# BatteryBoardV2.net
KiCad netlist of a schematic drawn in EAGLE
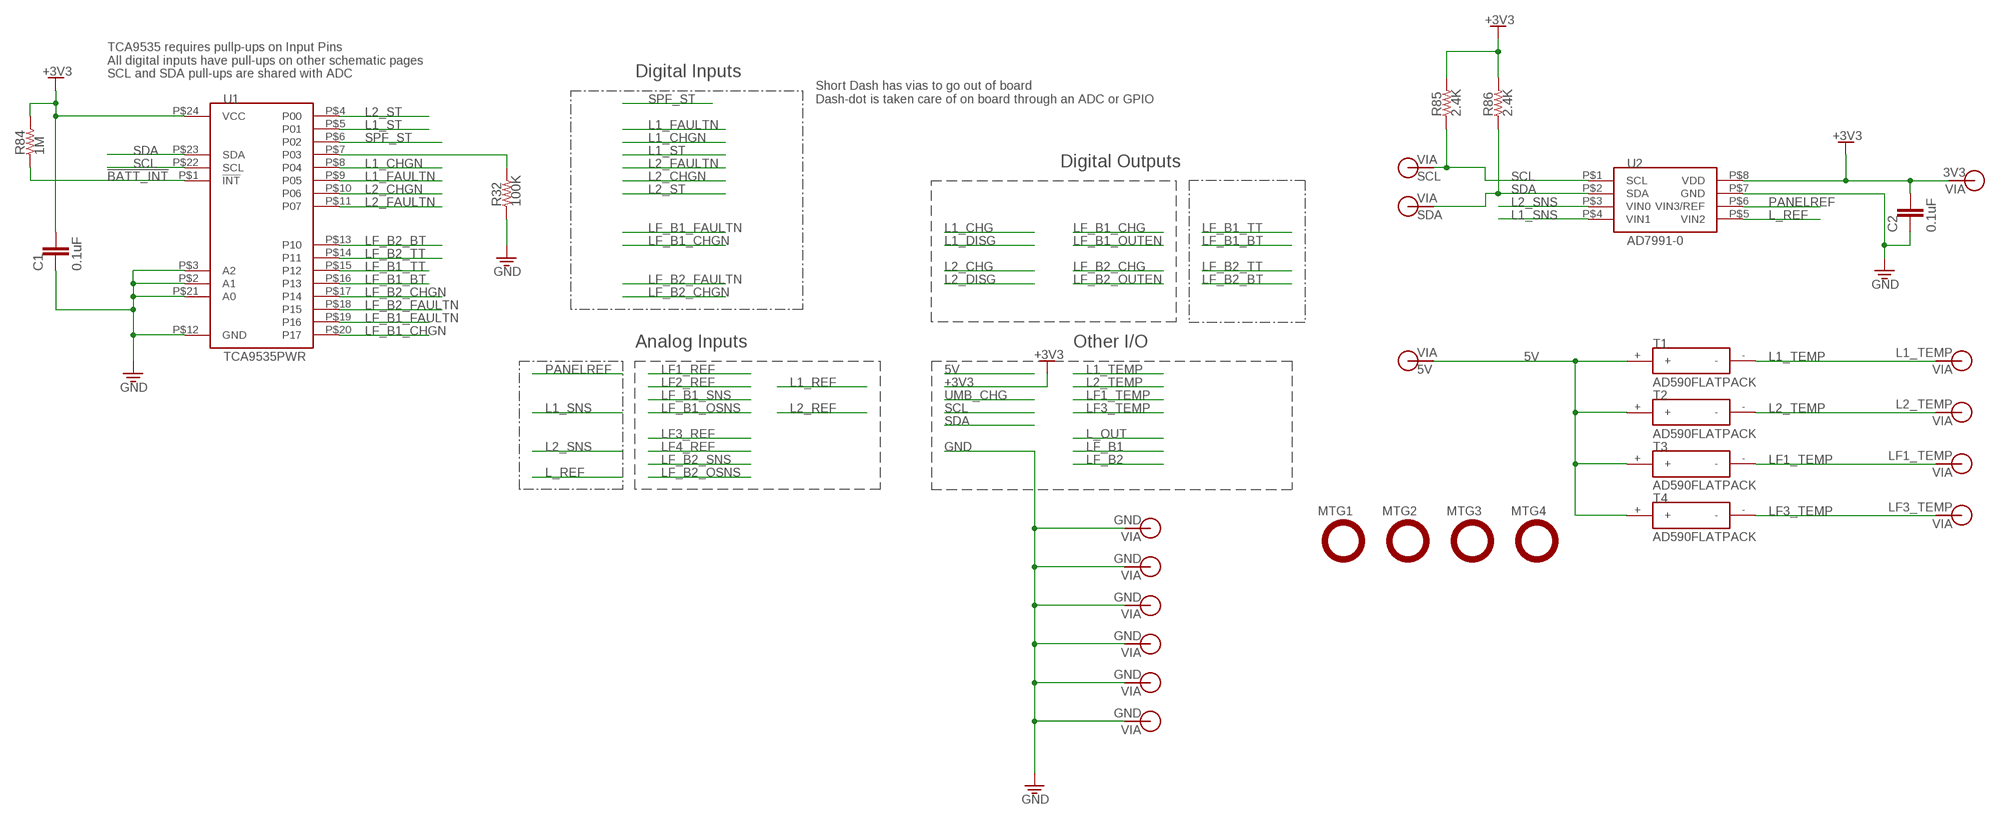
[diagram p0: schematic, sheet 1]
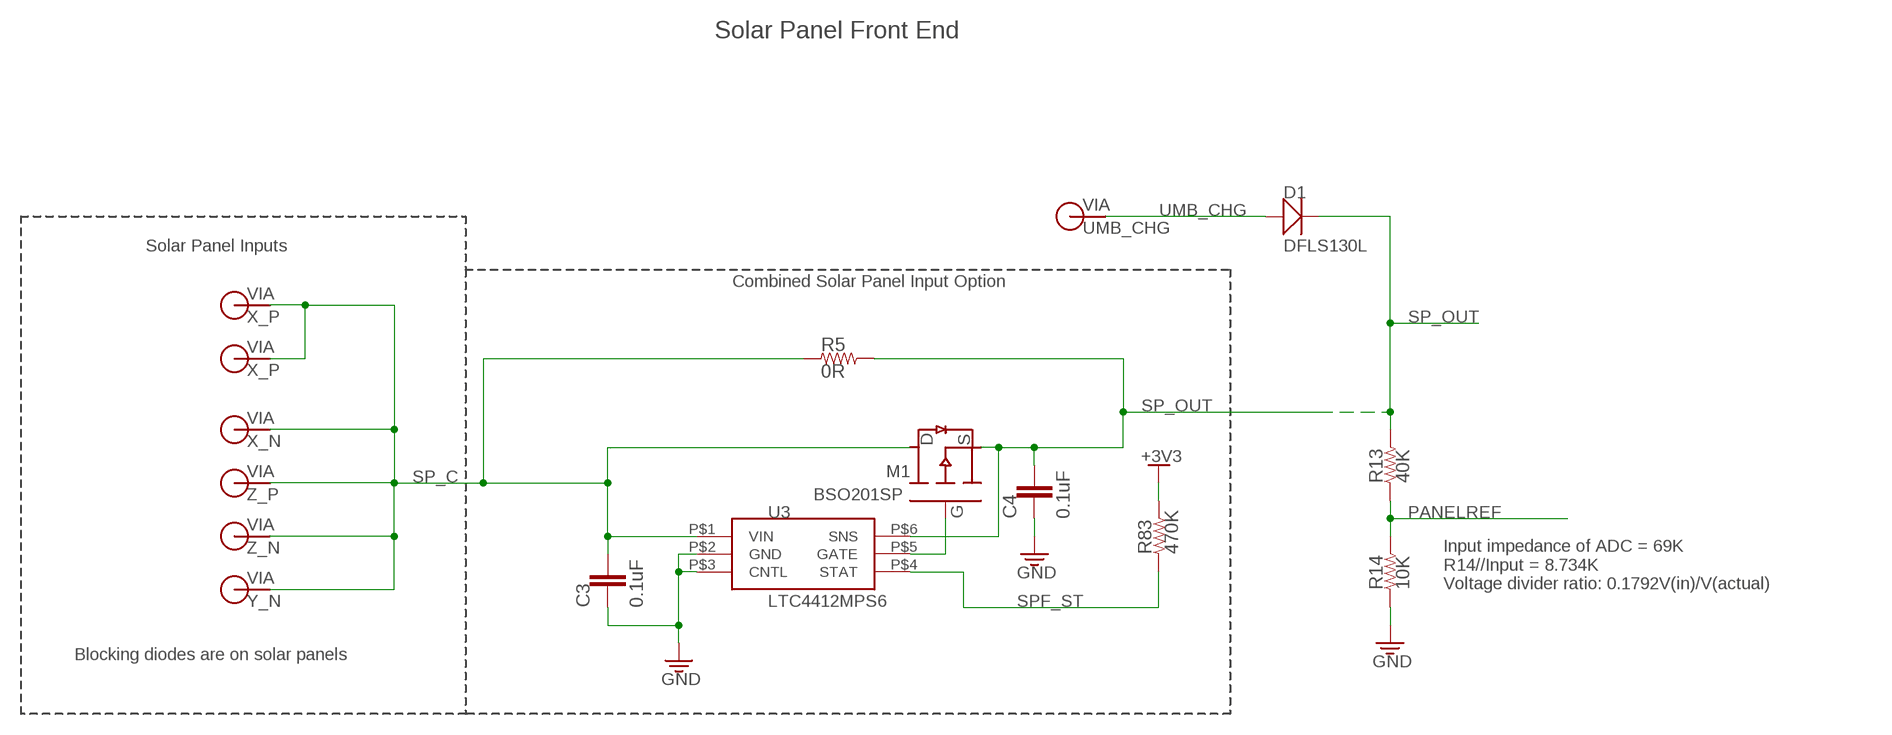
[diagram p1: schematic, sheet 2]
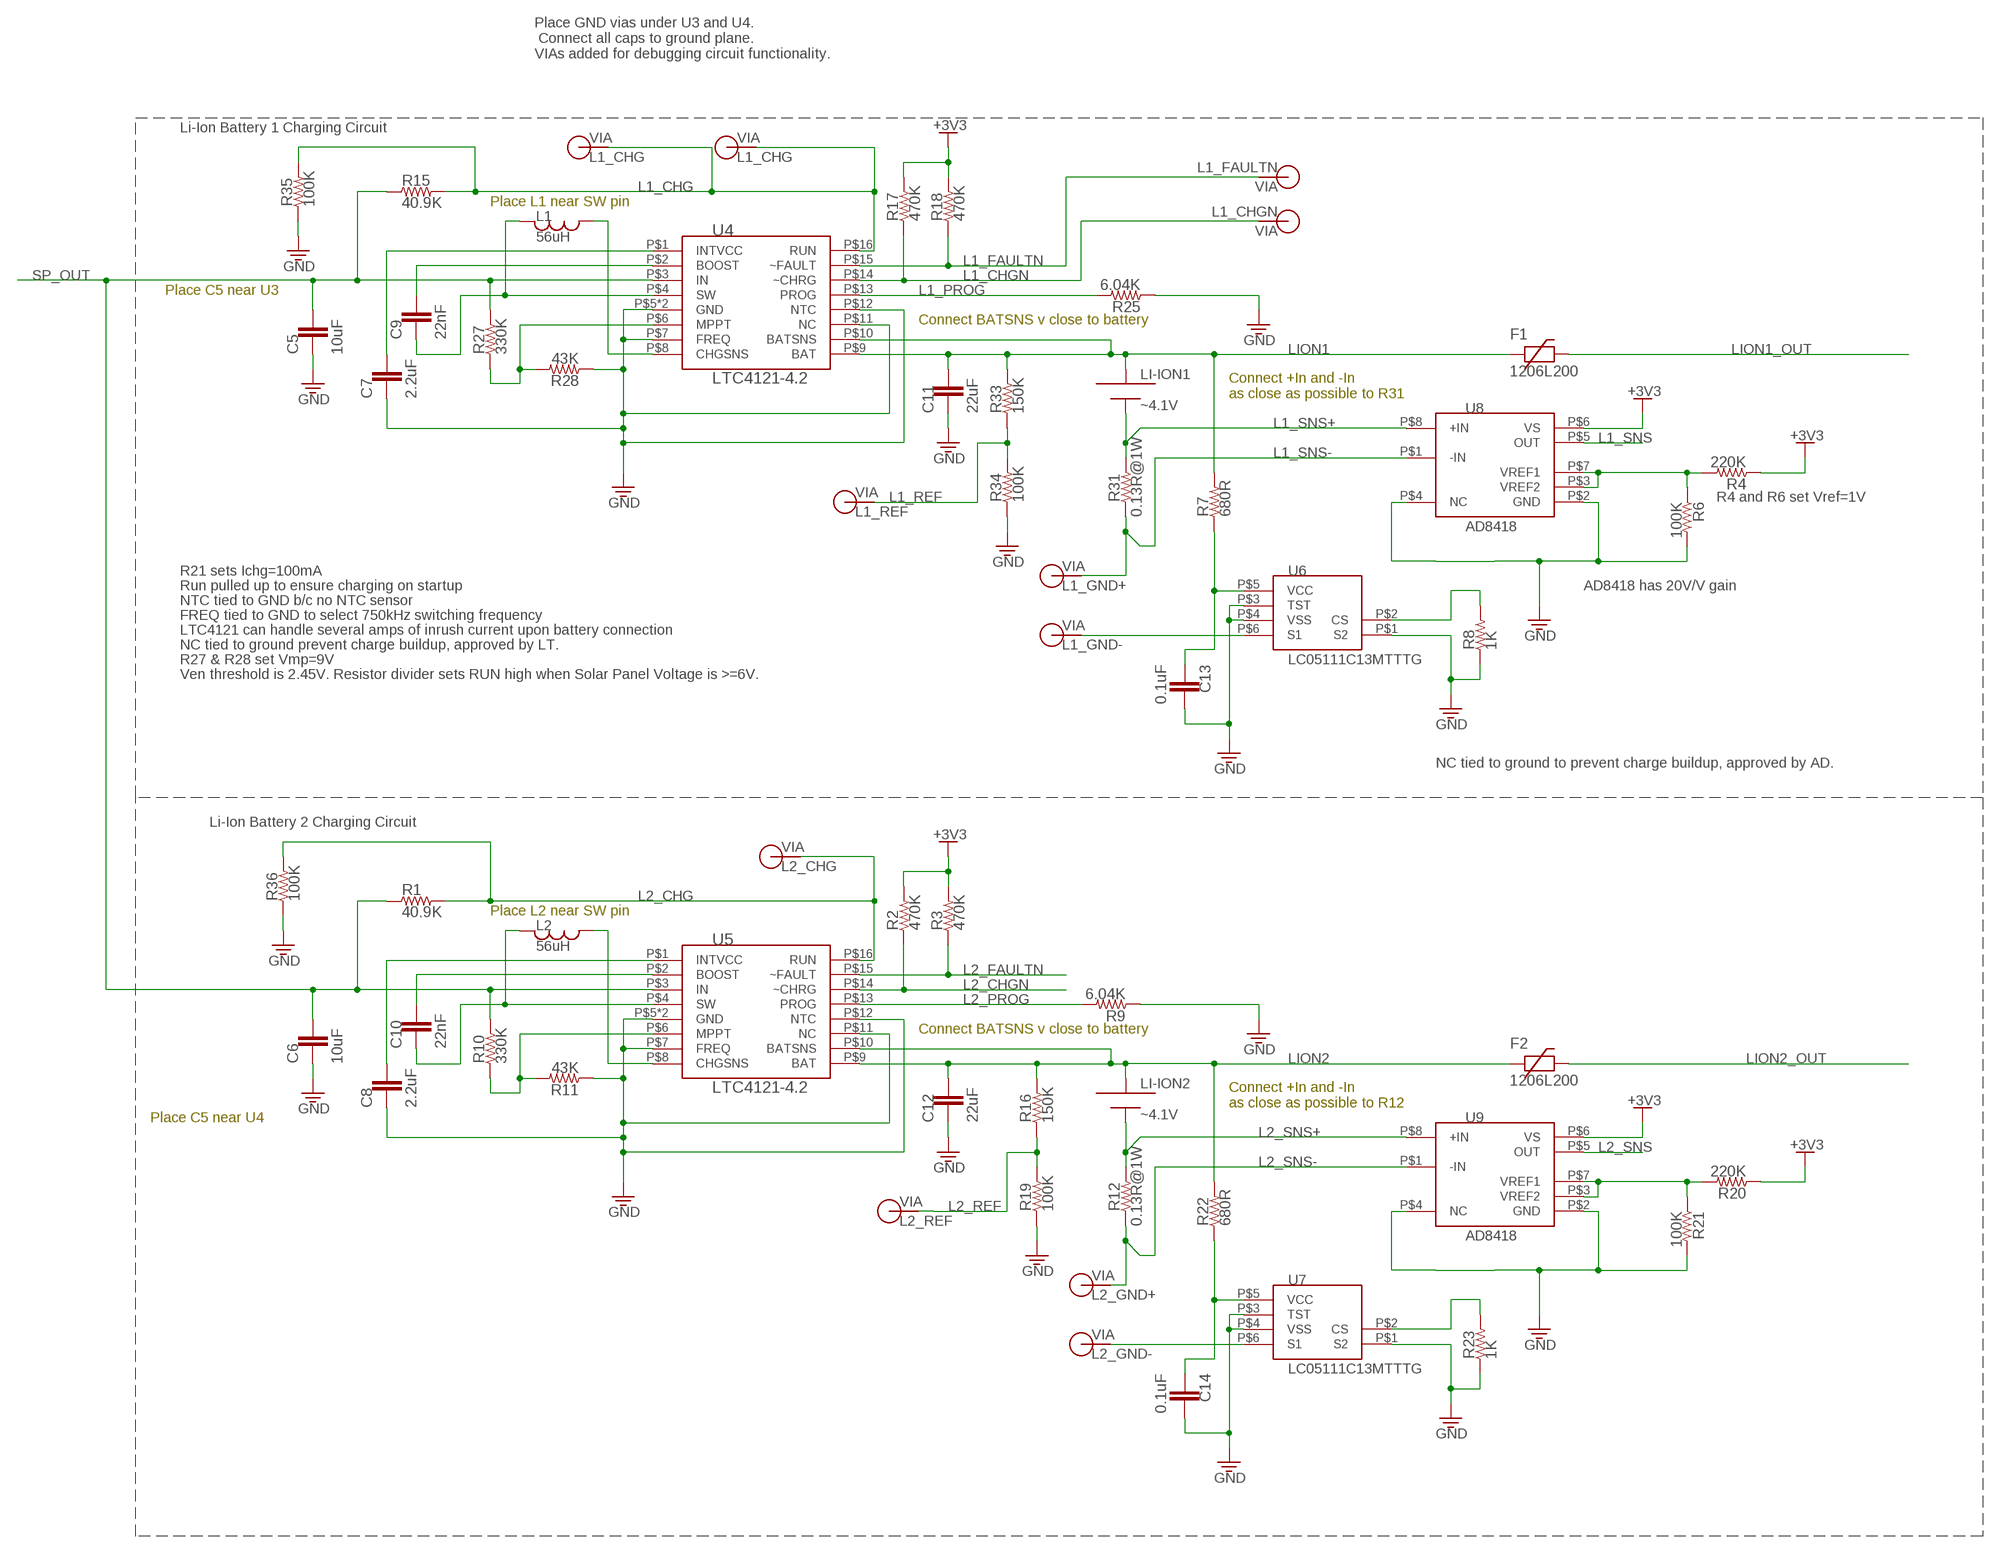
[diagram p2: schematic, sheet 3]
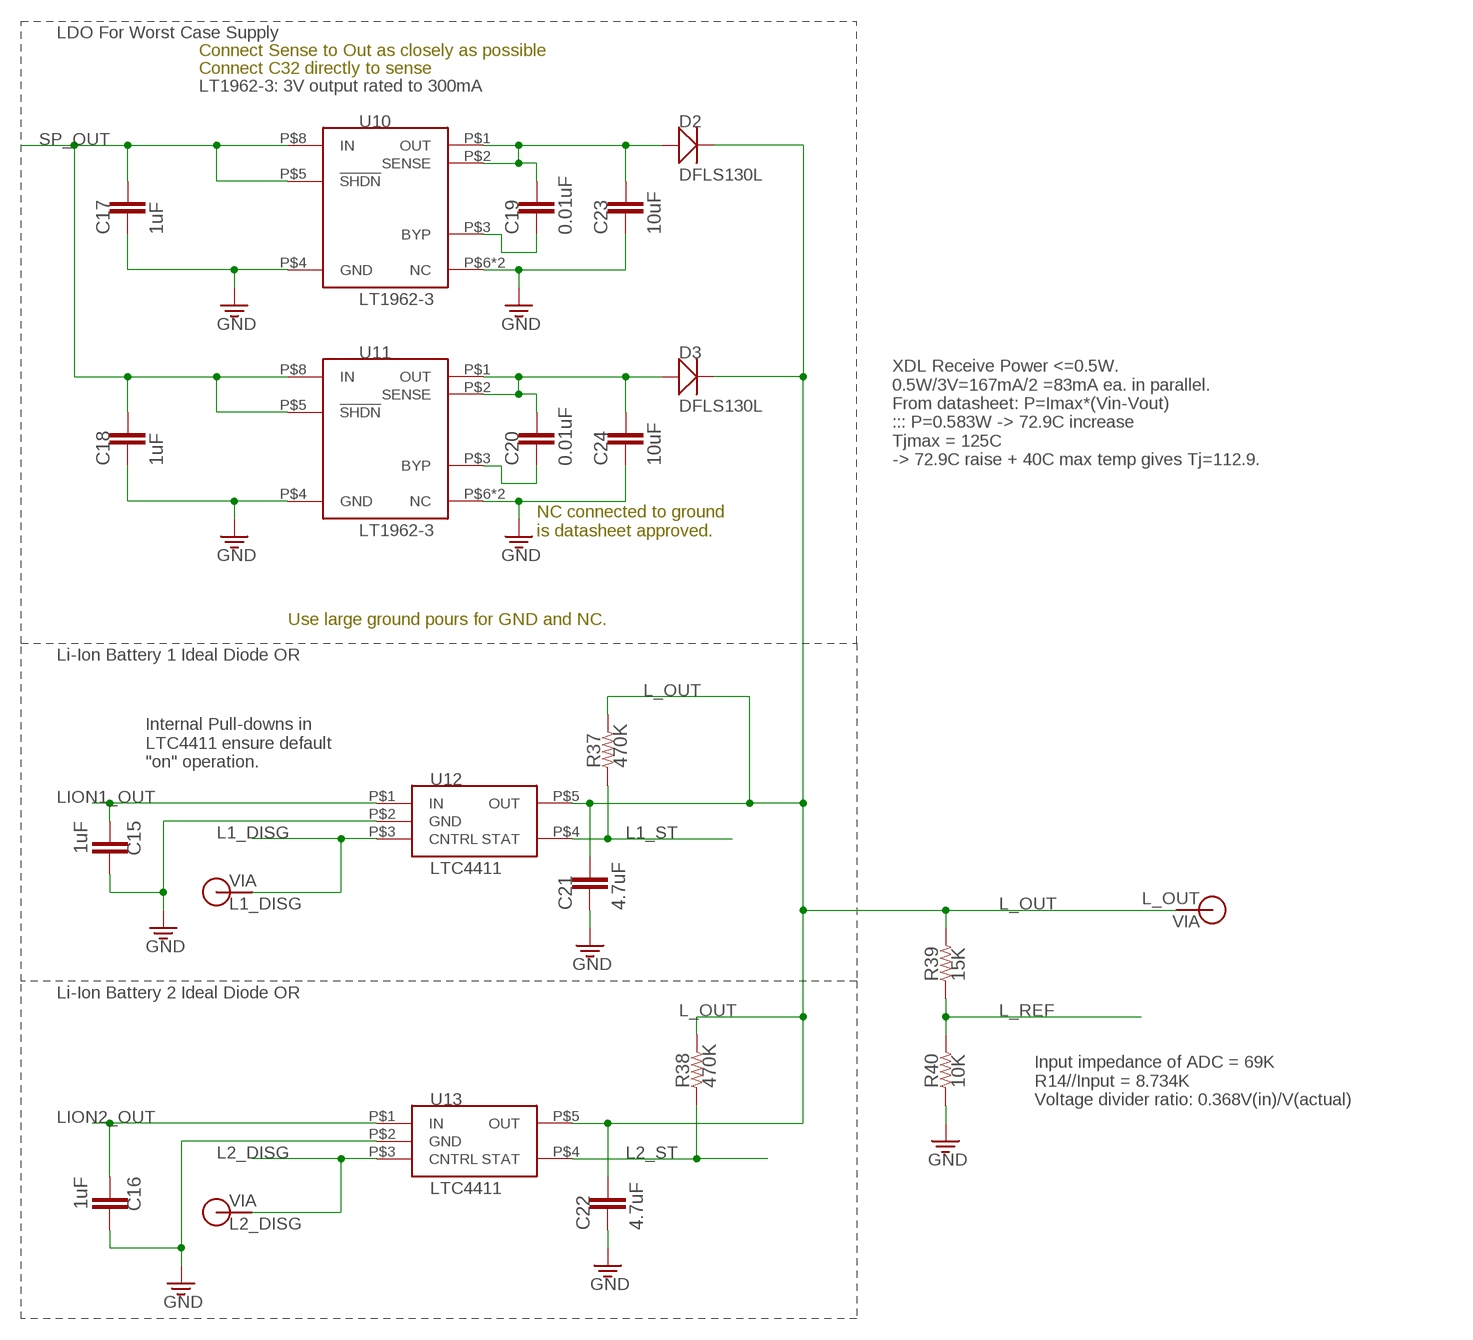
[diagram p3: schematic, sheet 4]
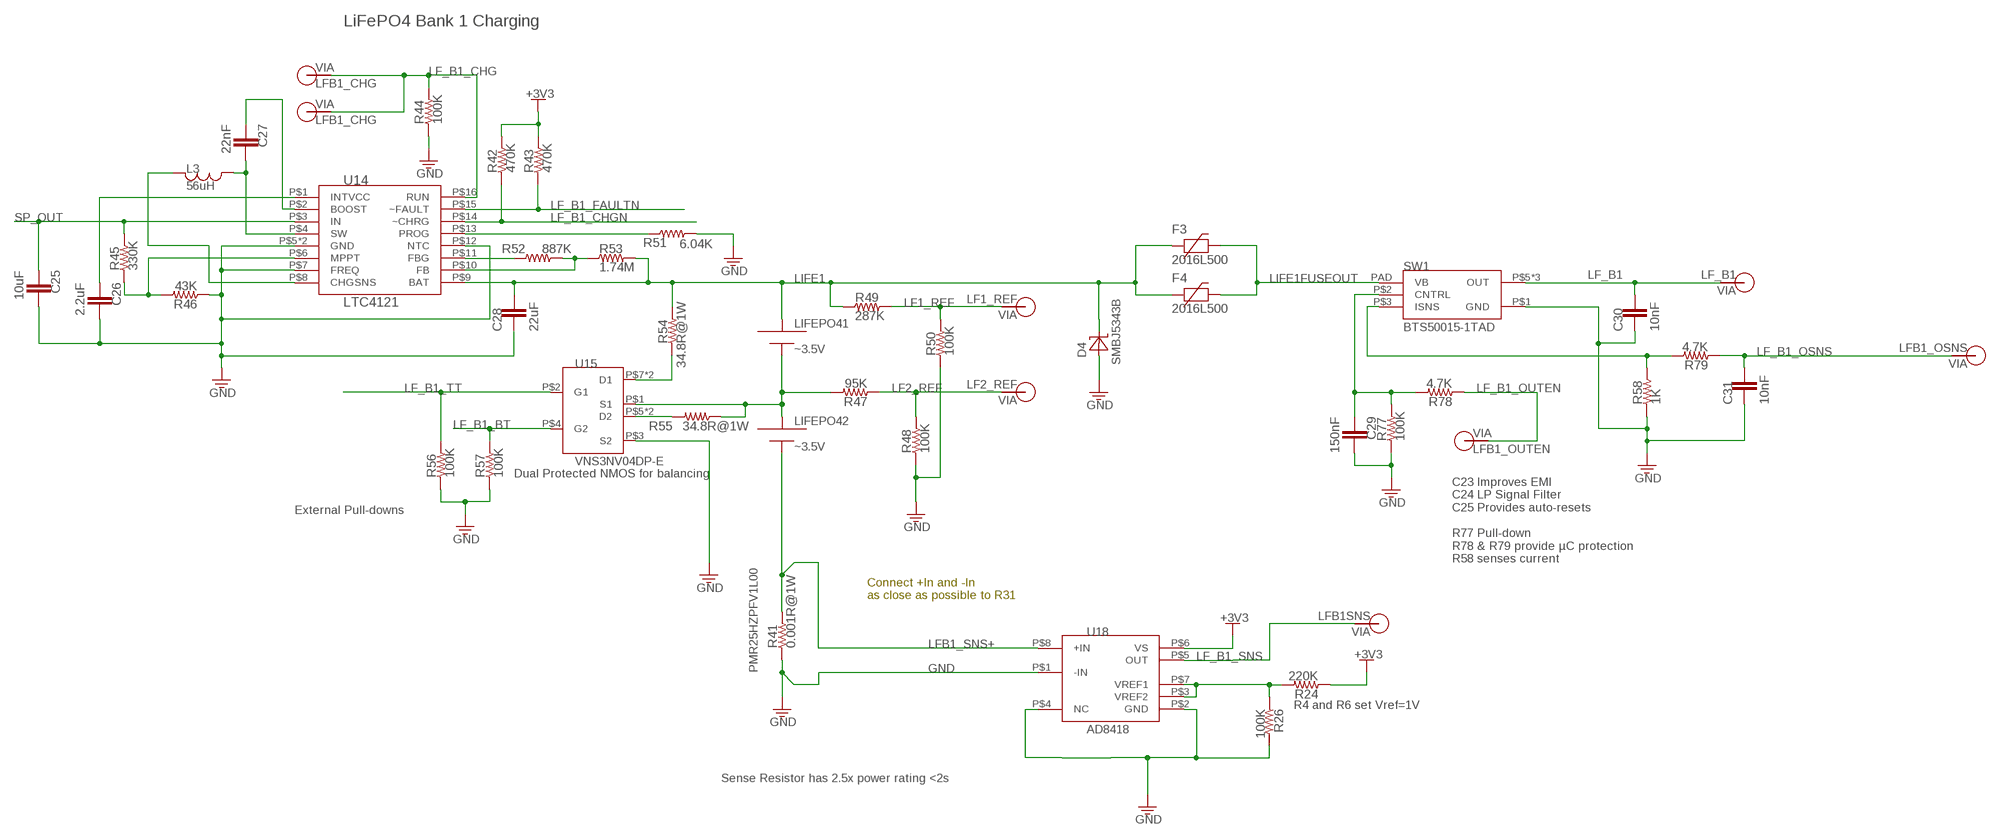
[diagram p4: schematic, sheet 5]
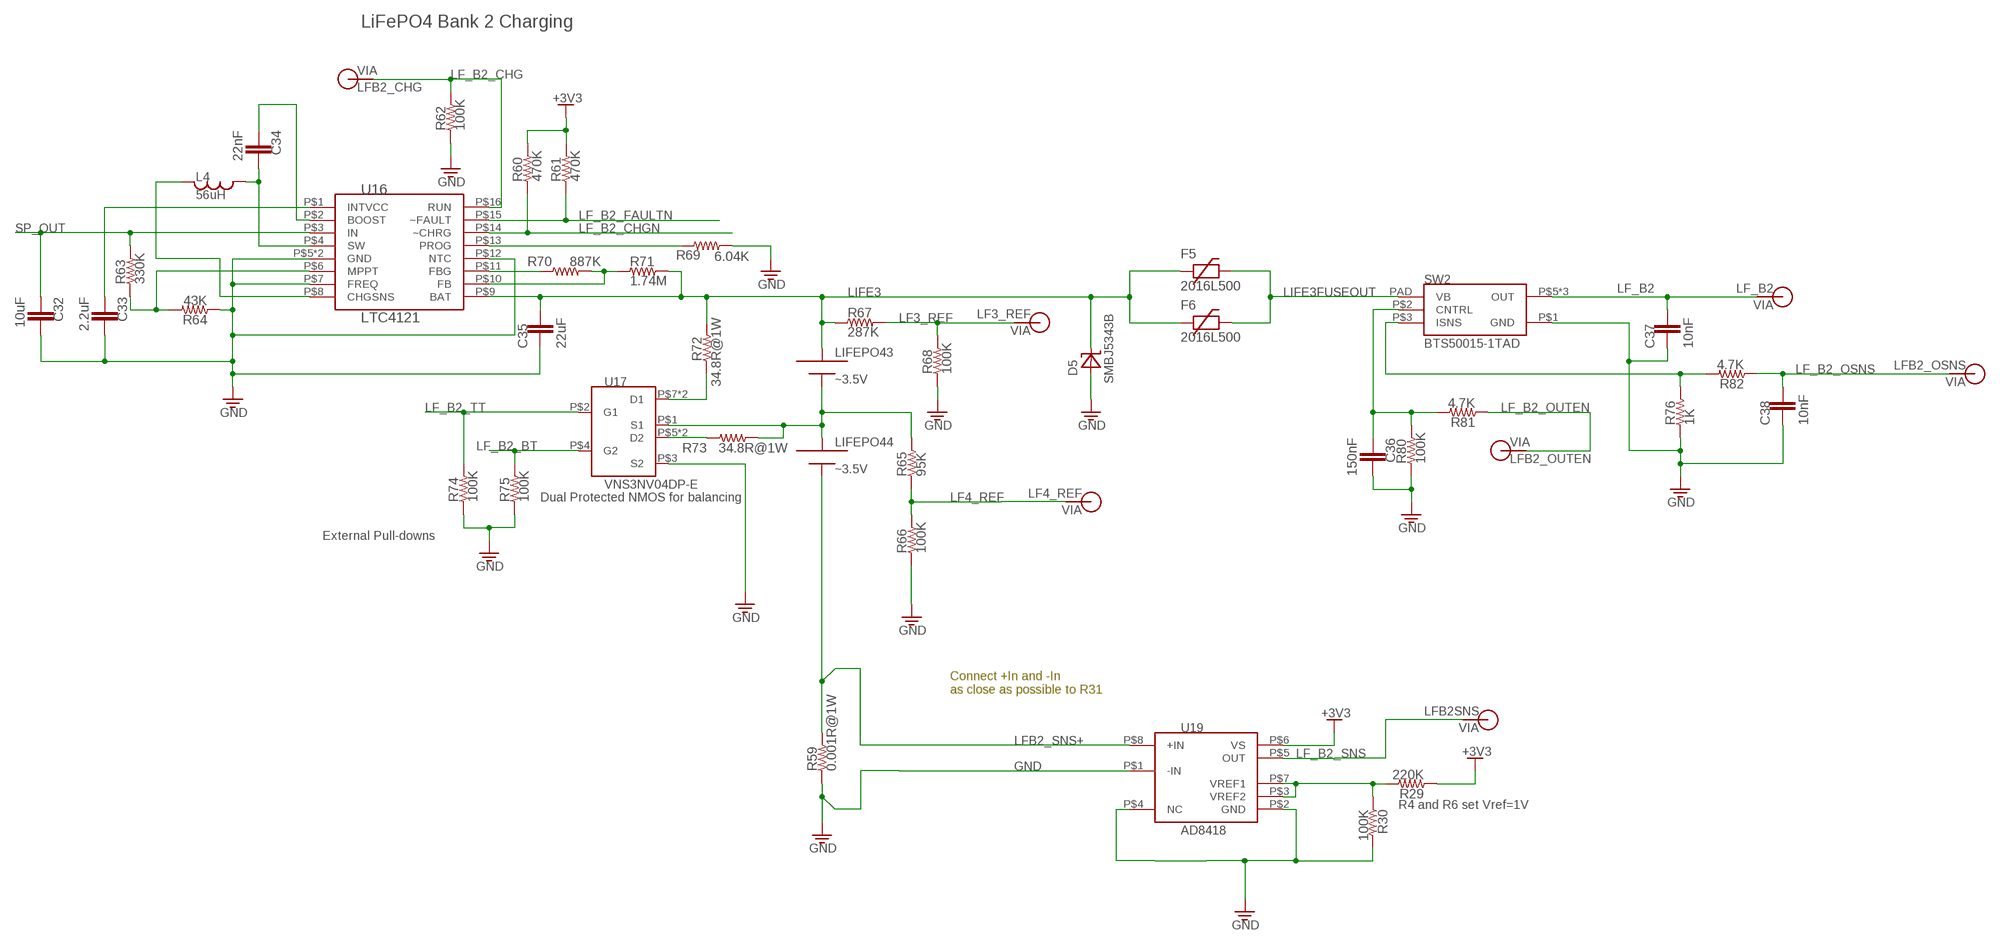
[diagram p5: schematic, sheet 6]

(export (version "E")
  (design (tool "Eeschema 10.0.6"))
  (components
    (comp (ref "C1")
      (value "0.1uF")
      (footprint "eagle-import:0805")
      (libsource (lib "eagle-import") (part "CAP0805"))
    )
    (comp (ref "C2")
      (value "0.1uF")
      (footprint "eagle-import:0805")
      (libsource (lib "eagle-import") (part "CAP0805"))
    )
    (comp (ref "MTG1")
      (value "MTG-NPTH-#2-CLOSE")
      (footprint "eagle-import:#2-CLOSE-NPTH")
      (libsource (lib "eagle-import") (part "MTG-NPTH-#2-CLOSE"))
    )
    (comp (ref "MTG2")
      (value "MTG-NPTH-#2-CLOSE")
      (footprint "eagle-import:#2-CLOSE-NPTH")
      (libsource (lib "eagle-import") (part "MTG-NPTH-#2-CLOSE"))
    )
    (comp (ref "MTG3")
      (value "MTG-NPTH-#2-CLOSE")
      (footprint "eagle-import:#2-CLOSE-NPTH")
      (libsource (lib "eagle-import") (part "MTG-NPTH-#2-CLOSE"))
    )
    (comp (ref "MTG4")
      (value "MTG-NPTH-#2-CLOSE")
      (footprint "eagle-import:#2-CLOSE-NPTH")
      (libsource (lib "eagle-import") (part "MTG-NPTH-#2-CLOSE"))
    )
    (comp (ref "R32")
      (value "100K")
      (footprint "eagle-import:0805")
      (libsource (lib "eagle-import") (part "RES0805"))
    )
    (comp (ref "R84")
      (value "1M")
      (footprint "eagle-import:0805")
      (libsource (lib "eagle-import") (part "RES0805"))
    )
    (comp (ref "R85")
      (value "2.4K")
      (footprint "eagle-import:0805")
      (libsource (lib "eagle-import") (part "RES0805"))
    )
    (comp (ref "R86")
      (value "2.4K")
      (footprint "eagle-import:0805")
      (libsource (lib "eagle-import") (part "RES0805"))
    )
    (comp (ref "T1")
      (value "AD590FLATPACK")
      (footprint "eagle-import:FLATPACK")
      (libsource (lib "eagle-import") (part "AD590FLATPACK"))
    )
    (comp (ref "T2")
      (value "AD590FLATPACK")
      (footprint "eagle-import:FLATPACK")
      (libsource (lib "eagle-import") (part "AD590FLATPACK"))
    )
    (comp (ref "T3")
      (value "AD590FLATPACK")
      (footprint "eagle-import:FLATPACK")
      (libsource (lib "eagle-import") (part "AD590FLATPACK"))
    )
    (comp (ref "T4")
      (value "AD590FLATPACK")
      (footprint "eagle-import:FLATPACK")
      (libsource (lib "eagle-import") (part "AD590FLATPACK"))
    )
    (comp (ref "U1")
      (value "TCA9535PWR")
      (footprint "eagle-import:TSSOP-24")
      (libsource (lib "eagle-import") (part "TCA9535PWR"))
    )
    (comp (ref "U2")
      (value "AD7991-0")
      (footprint "eagle-import:SOT-23-8")
      (libsource (lib "eagle-import") (part "AD7991-0"))
    )
    (comp (ref "V1")
      (value "GND")
      (footprint "eagle-import:VIA-120MIL")
      (libsource (lib "eagle-import") (part "VIA-120MIL"))
    )
    (comp (ref "V2")
      (value "GND")
      (footprint "eagle-import:VIA-120MIL")
      (libsource (lib "eagle-import") (part "VIA-120MIL"))
    )
    (comp (ref "V3")
      (value "GND")
      (footprint "eagle-import:VIA-60MIL-SQ")
      (libsource (lib "eagle-import") (part "VIA60MIL-SQ"))
    )
    (comp (ref "V4")
      (value "GND")
      (footprint "eagle-import:VIA-120MIL")
      (libsource (lib "eagle-import") (part "VIA-120MIL"))
    )
    (comp (ref "V5")
      (value "SCL")
      (footprint "eagle-import:VIA-60MIL")
      (libsource (lib "eagle-import") (part "VIA-60MIL"))
    )
    (comp (ref "V6")
      (value "SDA")
      (footprint "eagle-import:VIA-60MIL")
      (libsource (lib "eagle-import") (part "VIA-60MIL"))
    )
    (comp (ref "V7")
      (value "5V")
      (footprint "eagle-import:VIA-60MIL")
      (libsource (lib "eagle-import") (part "VIA-60MIL"))
    )
    (comp (ref "V8")
      (value "L1_TEMP")
      (footprint "eagle-import:VIA-60MIL")
      (libsource (lib "eagle-import") (part "VIA-60MIL"))
    )
    (comp (ref "V9")
      (value "L2_TEMP")
      (footprint "eagle-import:VIA-60MIL")
      (libsource (lib "eagle-import") (part "VIA-60MIL"))
    )
    (comp (ref "V10")
      (value "LF1_TEMP")
      (footprint "eagle-import:VIA-60MIL")
      (libsource (lib "eagle-import") (part "VIA-60MIL"))
    )
    (comp (ref "V11")
      (value "LF3_TEMP")
      (footprint "eagle-import:VIA-60MIL")
      (libsource (lib "eagle-import") (part "VIA-60MIL"))
    )
    (comp (ref "V12")
      (value "3V3")
      (footprint "eagle-import:VIA-60MIL")
      (libsource (lib "eagle-import") (part "VIA-60MIL"))
    )
    (comp (ref "V28")
      (value "GND")
      (footprint "eagle-import:VIA-60MIL-SQ")
      (libsource (lib "eagle-import") (part "VIA60MIL-SQ"))
    )
    (comp (ref "V36")
      (value "GND")
      (footprint "eagle-import:VIA-60MIL-SQ")
      (libsource (lib "eagle-import") (part "VIA60MIL-SQ"))
    )
    (comp (ref "C5")
      (value "10uF")
      (footprint "eagle-import:0805")
      (libsource (lib "eagle-import") (part "CAP0805"))
    )
    (comp (ref "C6")
      (value "10uF")
      (footprint "eagle-import:0805")
      (libsource (lib "eagle-import") (part "CAP0805"))
    )
    (comp (ref "C7")
      (value "2.2uF")
      (footprint "eagle-import:0805")
      (libsource (lib "eagle-import") (part "CAP0805"))
    )
    (comp (ref "C8")
      (value "2.2uF")
      (footprint "eagle-import:0805")
      (libsource (lib "eagle-import") (part "CAP0805"))
    )
    (comp (ref "C9")
      (value "22nF")
      (footprint "eagle-import:0805")
      (libsource (lib "eagle-import") (part "CAP0805"))
    )
    (comp (ref "C10")
      (value "22nF")
      (footprint "eagle-import:0805")
      (libsource (lib "eagle-import") (part "CAP0805"))
    )
    (comp (ref "C11")
      (value "22uF")
      (footprint "eagle-import:0805")
      (libsource (lib "eagle-import") (part "CAP0805"))
    )
    (comp (ref "C12")
      (value "22uF")
      (footprint "eagle-import:0805")
      (libsource (lib "eagle-import") (part "CAP0805"))
    )
    (comp (ref "C13")
      (value "0.1uF")
      (footprint "eagle-import:0805")
      (libsource (lib "eagle-import") (part "CAP0805"))
    )
    (comp (ref "C14")
      (value "0.1uF")
      (footprint "eagle-import:0805")
      (libsource (lib "eagle-import") (part "CAP0805"))
    )
    (comp (ref "F1")
      (value "1206L200")
      (footprint "eagle-import:1206")
      (libsource (lib "eagle-import") (part "PTCFUSE1206"))
    )
    (comp (ref "F2")
      (value "1206L200")
      (footprint "eagle-import:1206")
      (libsource (lib "eagle-import") (part "PTCFUSE1206"))
    )
    (comp (ref "L1")
      (value "56uH")
      (footprint "eagle-import:1812")
      (libsource (lib "eagle-import") (part "IND1812"))
    )
    (comp (ref "L2")
      (value "56uH")
      (footprint "eagle-import:1812")
      (libsource (lib "eagle-import") (part "IND1812"))
    )
    (comp (ref "LI-ION1")
      (value "~4.1V")
      (footprint "eagle-import:EQUISAT-BATTERY-VA")
      (libsource (lib "eagle-import") (part "LI-ION"))
    )
    (comp (ref "LI-ION2")
      (value "~4.1V")
      (footprint "eagle-import:EQUISAT-BATTERY-VA")
      (libsource (lib "eagle-import") (part "LI-ION"))
    )
    (comp (ref "R1")
      (value "40.9K")
      (footprint "eagle-import:0805")
      (libsource (lib "eagle-import") (part "RES0805"))
    )
    (comp (ref "R2")
      (value "470K")
      (footprint "eagle-import:0805")
      (libsource (lib "eagle-import") (part "RES0805"))
    )
    (comp (ref "R3")
      (value "470K")
      (footprint "eagle-import:0805")
      (libsource (lib "eagle-import") (part "RES0805"))
    )
    (comp (ref "R4")
      (value "220K")
      (footprint "eagle-import:0805")
      (libsource (lib "eagle-import") (part "RES0805"))
    )
    (comp (ref "R6")
      (value "100K")
      (footprint "eagle-import:0805")
      (libsource (lib "eagle-import") (part "RES0805"))
    )
    (comp (ref "R7")
      (value "680R")
      (footprint "eagle-import:0805")
      (libsource (lib "eagle-import") (part "RES0805"))
    )
    (comp (ref "R8")
      (value "1K")
      (footprint "eagle-import:0805")
      (libsource (lib "eagle-import") (part "RES0805"))
    )
    (comp (ref "R9")
      (value "6.04K")
      (footprint "eagle-import:0805")
      (libsource (lib "eagle-import") (part "RES0805"))
    )
    (comp (ref "R10")
      (value "330K")
      (footprint "eagle-import:0805")
      (libsource (lib "eagle-import") (part "RES0805"))
    )
    (comp (ref "R11")
      (value "43K")
      (footprint "eagle-import:0805")
      (libsource (lib "eagle-import") (part "RES0805"))
    )
    (comp (ref "R12")
      (value "0.13R@1W")
      (footprint "eagle-import:1210")
      (libsource (lib "eagle-import") (part "RES1210"))
    )
    (comp (ref "R15")
      (value "40.9K")
      (footprint "eagle-import:0805")
      (libsource (lib "eagle-import") (part "RES0805"))
    )
    (comp (ref "R16")
      (value "150K")
      (footprint "eagle-import:0805")
      (libsource (lib "eagle-import") (part "RES0805"))
    )
    (comp (ref "R17")
      (value "470K")
      (footprint "eagle-import:0805")
      (libsource (lib "eagle-import") (part "RES0805"))
    )
    (comp (ref "R18")
      (value "470K")
      (footprint "eagle-import:0805")
      (libsource (lib "eagle-import") (part "RES0805"))
    )
    (comp (ref "R19")
      (value "100K")
      (footprint "eagle-import:0805")
      (libsource (lib "eagle-import") (part "RES0805"))
    )
    (comp (ref "R20")
      (value "220K")
      (footprint "eagle-import:0805")
      (libsource (lib "eagle-import") (part "RES0805"))
    )
    (comp (ref "R21")
      (value "100K")
      (footprint "eagle-import:0805")
      (libsource (lib "eagle-import") (part "RES0805"))
    )
    (comp (ref "R22")
      (value "680R")
      (footprint "eagle-import:0805")
      (libsource (lib "eagle-import") (part "RES0805"))
    )
    (comp (ref "R23")
      (value "1K")
      (footprint "eagle-import:0805")
      (libsource (lib "eagle-import") (part "RES0805"))
    )
    (comp (ref "R25")
      (value "6.04K")
      (footprint "eagle-import:0805")
      (libsource (lib "eagle-import") (part "RES0805"))
    )
    (comp (ref "R27")
      (value "330K")
      (footprint "eagle-import:0805")
      (libsource (lib "eagle-import") (part "RES0805"))
    )
    (comp (ref "R28")
      (value "43K")
      (footprint "eagle-import:0805")
      (libsource (lib "eagle-import") (part "RES0805"))
    )
    (comp (ref "R31")
      (value "0.13R@1W")
      (footprint "eagle-import:1210")
      (libsource (lib "eagle-import") (part "RES1210"))
    )
    (comp (ref "R33")
      (value "150K")
      (footprint "eagle-import:0805")
      (libsource (lib "eagle-import") (part "RES0805"))
    )
    (comp (ref "R34")
      (value "100K")
      (footprint "eagle-import:0805")
      (libsource (lib "eagle-import") (part "RES0805"))
    )
    (comp (ref "R35")
      (value "100K")
      (footprint "eagle-import:0805")
      (libsource (lib "eagle-import") (part "RES0805"))
    )
    (comp (ref "R36")
      (value "100K")
      (footprint "eagle-import:0805")
      (libsource (lib "eagle-import") (part "RES0805"))
    )
    (comp (ref "U4")
      (value "LTC4121-4.2")
      (footprint "eagle-import:QFN-16-PAD")
      (libsource (lib "eagle-import") (part "LTC4121-4.2"))
    )
    (comp (ref "U5")
      (value "LTC4121-4.2")
      (footprint "eagle-import:QFN-16-PAD")
      (libsource (lib "eagle-import") (part "LTC4121-4.2"))
    )
    (comp (ref "U6")
      (value "LC05111C13MTTTG")
      (footprint "eagle-import:WDFN6")
      (libsource (lib "eagle-import") (part "LC05111C13MTTTG"))
    )
    (comp (ref "U7")
      (value "LC05111C13MTTTG")
      (footprint "eagle-import:WDFN6")
      (libsource (lib "eagle-import") (part "LC05111C13MTTTG"))
    )
    (comp (ref "U8")
      (value "AD8418")
      (footprint "eagle-import:MSOP-8")
      (libsource (lib "eagle-import") (part "AD8418"))
    )
    (comp (ref "U9")
      (value "AD8418")
      (footprint "eagle-import:MSOP-8")
      (libsource (lib "eagle-import") (part "AD8418"))
    )
    (comp (ref "V20")
      (value "L1_CHG")
      (footprint "eagle-import:VIA-60MIL")
      (libsource (lib "eagle-import") (part "VIA-60MIL"))
    )
    (comp (ref "V21")
      (value "L1_REF")
      (footprint "eagle-import:VIA-60MIL")
      (libsource (lib "eagle-import") (part "VIA-60MIL"))
    )
    (comp (ref "V22")
      (value "L1_GND+")
      (footprint "eagle-import:VIA-60MIL")
      (libsource (lib "eagle-import") (part "VIA-60MIL"))
    )
    (comp (ref "V23")
      (value "L1_GND-")
      (footprint "eagle-import:VIA-60MIL")
      (libsource (lib "eagle-import") (part "VIA-60MIL"))
    )
    (comp (ref "V24")
      (value "L2_GND+")
      (footprint "eagle-import:VIA-60MIL")
      (libsource (lib "eagle-import") (part "VIA-60MIL"))
    )
    (comp (ref "V25")
      (value "L2_GND-")
      (footprint "eagle-import:VIA-60MIL")
      (libsource (lib "eagle-import") (part "VIA-60MIL"))
    )
    (comp (ref "V26")
      (value "L1_FAULTN")
      (footprint "eagle-import:VIA-60MIL-SQ")
      (libsource (lib "eagle-import") (part "VIA60MIL-SQ"))
    )
    (comp (ref "V27")
      (value "L1_CHGN")
      (footprint "eagle-import:VIA-60MIL-SQ")
      (libsource (lib "eagle-import") (part "VIA60MIL-SQ"))
    )
    (comp (ref "V31")
      (value "L2_REF")
      (footprint "eagle-import:VIA-60MIL")
      (libsource (lib "eagle-import") (part "VIA-60MIL"))
    )
    (comp (ref "V33")
      (value "L2_CHG")
      (footprint "eagle-import:VIA-60MIL")
      (libsource (lib "eagle-import") (part "VIA-60MIL"))
    )
    (comp (ref "V48")
      (value "L1_CHG")
      (footprint "eagle-import:VIA-60MIL-SQ")
      (libsource (lib "eagle-import") (part "VIA60MIL-SQ"))
    )
    (comp (ref "C32")
      (value "10uF")
      (footprint "eagle-import:0805")
      (libsource (lib "eagle-import") (part "CAP0805"))
    )
    (comp (ref "C33")
      (value "2.2uF")
      (footprint "eagle-import:0805")
      (libsource (lib "eagle-import") (part "CAP0805"))
    )
    (comp (ref "C34")
      (value "22nF")
      (footprint "eagle-import:0805")
      (libsource (lib "eagle-import") (part "CAP0805"))
    )
    (comp (ref "C35")
      (value "22uF")
      (footprint "eagle-import:0805")
      (libsource (lib "eagle-import") (part "CAP0805"))
    )
    (comp (ref "C36")
      (value "150nF")
      (footprint "eagle-import:0805")
      (libsource (lib "eagle-import") (part "CAP0805"))
    )
    (comp (ref "C37")
      (value "10nF")
      (footprint "eagle-import:0805")
      (libsource (lib "eagle-import") (part "CAP0805"))
    )
    (comp (ref "C38")
      (value "10nF")
      (footprint "eagle-import:0805")
      (libsource (lib "eagle-import") (part "CAP0805"))
    )
    (comp (ref "D5")
      (value "SMBJ5343B")
      (footprint "eagle-import:DO214AA")
      (libsource (lib "eagle-import") (part "SMBJ5343B"))
    )
    (comp (ref "F5")
      (value "2016L500")
      (footprint "eagle-import:2016")
      (libsource (lib "eagle-import") (part "2016L500"))
    )
    (comp (ref "F6")
      (value "2016L500")
      (footprint "eagle-import:2016")
      (libsource (lib "eagle-import") (part "2016L500"))
    )
    (comp (ref "L4")
      (value "56uH")
      (footprint "eagle-import:1812")
      (libsource (lib "eagle-import") (part "IND1812"))
    )
    (comp (ref "LIFEPO43")
      (value "~3.5V")
      (footprint "eagle-import:EQUISAT-BATTERY-VA")
      (libsource (lib "eagle-import") (part "LIFEPO4VA"))
    )
    (comp (ref "LIFEPO44")
      (value "~3.5V")
      (footprint "eagle-import:EQUISAT-BATTERY-VB")
      (libsource (lib "eagle-import") (part "LIFEPO4VB"))
    )
    (comp (ref "R29")
      (value "220K")
      (footprint "eagle-import:0805")
      (libsource (lib "eagle-import") (part "RES0805"))
    )
    (comp (ref "R30")
      (value "100K")
      (footprint "eagle-import:0805")
      (libsource (lib "eagle-import") (part "RES0805"))
    )
    (comp (ref "R59")
      (value "0.001R@1W")
      (footprint "eagle-import:1210")
      (libsource (lib "eagle-import") (part "RES1210"))
    )
    (comp (ref "R60")
      (value "470K")
      (footprint "eagle-import:0805")
      (libsource (lib "eagle-import") (part "RES0805"))
    )
    (comp (ref "R61")
      (value "470K")
      (footprint "eagle-import:0805")
      (libsource (lib "eagle-import") (part "RES0805"))
    )
    (comp (ref "R62")
      (value "100K")
      (footprint "eagle-import:0805")
      (libsource (lib "eagle-import") (part "RES0805"))
    )
    (comp (ref "R63")
      (value "330K")
      (footprint "eagle-import:0805")
      (libsource (lib "eagle-import") (part "RES0805"))
    )
    (comp (ref "R64")
      (value "43K")
      (footprint "eagle-import:0805")
      (libsource (lib "eagle-import") (part "RES0805"))
    )
    (comp (ref "R65")
      (value "95K")
      (footprint "eagle-import:0805")
      (libsource (lib "eagle-import") (part "RES0805"))
    )
    (comp (ref "R66")
      (value "100K")
      (footprint "eagle-import:0805")
      (libsource (lib "eagle-import") (part "RES0805"))
    )
    (comp (ref "R67")
      (value "287K")
      (footprint "eagle-import:0805")
      (libsource (lib "eagle-import") (part "RES0805"))
    )
    (comp (ref "R68")
      (value "100K")
      (footprint "eagle-import:0805")
      (libsource (lib "eagle-import") (part "RES0805"))
    )
    (comp (ref "R69")
      (value "6.04K")
      (footprint "eagle-import:0805")
      (libsource (lib "eagle-import") (part "RES0805"))
    )
    (comp (ref "R70")
      (value "887K")
      (footprint "eagle-import:0805")
      (libsource (lib "eagle-import") (part "RES0805"))
    )
    (comp (ref "R71")
      (value "1.74M")
      (footprint "eagle-import:0805")
      (libsource (lib "eagle-import") (part "RES0805"))
    )
    (comp (ref "R72")
      (value "34.8R@1W")
      (footprint "eagle-import:1210")
      (libsource (lib "eagle-import") (part "RES1210"))
    )
    (comp (ref "R73")
      (value "34.8R@1W")
      (footprint "eagle-import:1210")
      (libsource (lib "eagle-import") (part "RES1210"))
    )
    (comp (ref "R74")
      (value "100K")
      (footprint "eagle-import:0805")
      (libsource (lib "eagle-import") (part "RES0805"))
    )
    (comp (ref "R75")
      (value "100K")
      (footprint "eagle-import:0805")
      (libsource (lib "eagle-import") (part "RES0805"))
    )
    (comp (ref "R76")
      (value "1K")
      (footprint "eagle-import:0805")
      (libsource (lib "eagle-import") (part "RES0805"))
    )
    (comp (ref "R80")
      (value "100K")
      (footprint "eagle-import:0805")
      (libsource (lib "eagle-import") (part "RES0805"))
    )
    (comp (ref "R81")
      (value "4.7K")
      (footprint "eagle-import:0805")
      (libsource (lib "eagle-import") (part "RES0805"))
    )
    (comp (ref "R82")
      (value "4.7K")
      (footprint "eagle-import:0805")
      (libsource (lib "eagle-import") (part "RES0805"))
    )
    (comp (ref "SW2")
      (value "BTS50015-1TAD")
      (footprint "eagle-import:TO-263-7-8")
      (libsource (lib "eagle-import") (part "BTS50015-1TAD"))
    )
    (comp (ref "U16")
      (value "LTC4121")
      (footprint "eagle-import:QFN-16-PAD")
      (libsource (lib "eagle-import") (part "LTC4121"))
    )
    (comp (ref "U17")
      (value "VNS3NV04DP-E")
      (footprint "eagle-import:SO-8")
      (libsource (lib "eagle-import") (part "VNS3NV04DP-E"))
    )
    (comp (ref "U19")
      (value "AD8418")
      (footprint "eagle-import:MSOP-8")
      (libsource (lib "eagle-import") (part "AD8418"))
    )
    (comp (ref "V44")
      (value "LFB2SNS")
      (footprint "eagle-import:VIA-60MIL")
      (libsource (lib "eagle-import") (part "VIA-60MIL"))
    )
    (comp (ref "V47")
      (value "LFB2_CHG")
      (footprint "eagle-import:VIA-60MIL")
      (libsource (lib "eagle-import") (part "VIA-60MIL"))
    )
    (comp (ref "V49")
      (value "LF3_REF")
      (footprint "eagle-import:VIA-60MIL")
      (libsource (lib "eagle-import") (part "VIA-60MIL"))
    )
    (comp (ref "V50")
      (value "LF4_REF")
      (footprint "eagle-import:VIA-60MIL")
      (libsource (lib "eagle-import") (part "VIA-60MIL"))
    )
    (comp (ref "V51")
      (value "LFB2_OUTEN")
      (footprint "eagle-import:VIA-60MIL")
      (libsource (lib "eagle-import") (part "VIA-60MIL"))
    )
    (comp (ref "V53")
      (value "LF_B2")
      (footprint "eagle-import:VIA-120MIL")
      (libsource (lib "eagle-import") (part "VIA-120MIL"))
    )
    (comp (ref "V99")
      (value "LFB2_OSNS")
      (footprint "eagle-import:VIA-60MIL")
      (libsource (lib "eagle-import") (part "VIA-60MIL"))
    )
    (comp (ref "C3")
      (value "0.1uF")
      (footprint "eagle-import:0805")
      (libsource (lib "eagle-import") (part "CAP0805"))
    )
    (comp (ref "C4")
      (value "0.1uF")
      (footprint "eagle-import:0805")
      (libsource (lib "eagle-import") (part "CAP0805"))
    )
    (comp (ref "D1")
      (value "DFLS130L")
      (footprint "eagle-import:PWRDI-123")
      (libsource (lib "eagle-import") (part "DFLS130L"))
    )
    (comp (ref "M1")
      (value "BSO201SP")
      (footprint "eagle-import:SO-8")
      (libsource (lib "eagle-import") (part "BSO201SP"))
    )
    (comp (ref "R5")
      (value "0R")
      (footprint "eagle-import:0805")
      (libsource (lib "eagle-import") (part "RES0805"))
    )
    (comp (ref "R13")
      (value "40K")
      (footprint "eagle-import:0805")
      (libsource (lib "eagle-import") (part "RES0805"))
    )
    (comp (ref "R14")
      (value "10K")
      (footprint "eagle-import:0805")
      (libsource (lib "eagle-import") (part "RES0805"))
    )
    (comp (ref "R83")
      (value "470K")
      (footprint "eagle-import:0805")
      (libsource (lib "eagle-import") (part "RES0805"))
    )
    (comp (ref "U3")
      (value "LTC4412MPS6")
      (footprint "eagle-import:TSOT23-6")
      (libsource (lib "eagle-import") (part "LTC4412"))
    )
    (comp (ref "V13")
      (value "X_P")
      (footprint "eagle-import:VIA-60MIL")
      (libsource (lib "eagle-import") (part "VIA-60MIL"))
    )
    (comp (ref "V14")
      (value "X_P")
      (footprint "eagle-import:VIA-60MIL-SQ")
      (libsource (lib "eagle-import") (part "VIA60MIL-SQ"))
    )
    (comp (ref "V15")
      (value "X_N")
      (footprint "eagle-import:VIA-60MIL")
      (libsource (lib "eagle-import") (part "VIA-60MIL"))
    )
    (comp (ref "V16")
      (value "Z_P")
      (footprint "eagle-import:VIA-60MIL")
      (libsource (lib "eagle-import") (part "VIA-60MIL"))
    )
    (comp (ref "V17")
      (value "Z_N")
      (footprint "eagle-import:VIA-60MIL")
      (libsource (lib "eagle-import") (part "VIA-60MIL"))
    )
    (comp (ref "V18")
      (value "Y_N")
      (footprint "eagle-import:VIA-60MIL")
      (libsource (lib "eagle-import") (part "VIA-60MIL"))
    )
    (comp (ref "V19")
      (value "UMB_CHG")
      (footprint "eagle-import:VIA-60MIL")
      (libsource (lib "eagle-import") (part "VIA-60MIL"))
    )
    (comp (ref "C15")
      (value "1uF")
      (footprint "eagle-import:0805")
      (libsource (lib "eagle-import") (part "CAP0805"))
    )
    (comp (ref "C16")
      (value "1uF")
      (footprint "eagle-import:0805")
      (libsource (lib "eagle-import") (part "CAP0805"))
    )
    (comp (ref "C17")
      (value "1uF")
      (footprint "eagle-import:0805")
      (libsource (lib "eagle-import") (part "CAP0805"))
    )
    (comp (ref "C18")
      (value "1uF")
      (footprint "eagle-import:0805")
      (libsource (lib "eagle-import") (part "CAP0805"))
    )
    (comp (ref "C19")
      (value "0.01uF")
      (footprint "eagle-import:0805")
      (libsource (lib "eagle-import") (part "CAP0805"))
    )
    (comp (ref "C20")
      (value "0.01uF")
      (footprint "eagle-import:0805")
      (libsource (lib "eagle-import") (part "CAP0805"))
    )
    (comp (ref "C21")
      (value "4.7uF")
      (footprint "eagle-import:0805")
      (libsource (lib "eagle-import") (part "CAP0805"))
    )
    (comp (ref "C22")
      (value "4.7uF")
      (footprint "eagle-import:0805")
      (libsource (lib "eagle-import") (part "CAP0805"))
    )
    (comp (ref "C23")
      (value "10uF")
      (footprint "eagle-import:0805")
      (libsource (lib "eagle-import") (part "CAP0805"))
    )
    (comp (ref "C24")
      (value "10uF")
      (footprint "eagle-import:0805")
      (libsource (lib "eagle-import") (part "CAP0805"))
    )
    (comp (ref "D2")
      (value "DFLS130L")
      (footprint "eagle-import:PWRDI-123")
      (libsource (lib "eagle-import") (part "DFLS130L"))
    )
    (comp (ref "D3")
      (value "DFLS130L")
      (footprint "eagle-import:PWRDI-123")
      (libsource (lib "eagle-import") (part "DFLS130L"))
    )
    (comp (ref "R37")
      (value "470K")
      (footprint "eagle-import:0805")
      (libsource (lib "eagle-import") (part "RES0805"))
    )
    (comp (ref "R38")
      (value "470K")
      (footprint "eagle-import:0805")
      (libsource (lib "eagle-import") (part "RES0805"))
    )
    (comp (ref "R39")
      (value "15K")
      (footprint "eagle-import:0805")
      (libsource (lib "eagle-import") (part "RES0805"))
    )
    (comp (ref "R40")
      (value "10K")
      (footprint "eagle-import:0805")
      (libsource (lib "eagle-import") (part "RES0805"))
    )
    (comp (ref "U10")
      (value "LT1962-3")
      (footprint "eagle-import:MSOP-8")
      (libsource (lib "eagle-import") (part "LT1962-3"))
    )
    (comp (ref "U11")
      (value "LT1962-3")
      (footprint "eagle-import:MSOP-8")
      (libsource (lib "eagle-import") (part "LT1962-3"))
    )
    (comp (ref "U12")
      (value "LTC4411")
      (footprint "eagle-import:TSOT23-5")
      (libsource (lib "eagle-import") (part "LTC4411"))
    )
    (comp (ref "U13")
      (value "LTC4411")
      (footprint "eagle-import:TSOT23-5")
      (libsource (lib "eagle-import") (part "LTC4411"))
    )
    (comp (ref "V29")
      (value "L1_DISG")
      (footprint "eagle-import:VIA-60MIL")
      (libsource (lib "eagle-import") (part "VIA-60MIL"))
    )
    (comp (ref "V30")
      (value "L2_DISG")
      (footprint "eagle-import:VIA-60MIL")
      (libsource (lib "eagle-import") (part "VIA-60MIL"))
    )
    (comp (ref "V34")
      (value "L_OUT")
      (footprint "eagle-import:VIA-120MIL")
      (libsource (lib "eagle-import") (part "VIA-120MIL"))
    )
    (comp (ref "C25")
      (value "10uF")
      (footprint "eagle-import:0805")
      (libsource (lib "eagle-import") (part "CAP0805"))
    )
    (comp (ref "C26")
      (value "2.2uF")
      (footprint "eagle-import:0805")
      (libsource (lib "eagle-import") (part "CAP0805"))
    )
    (comp (ref "C27")
      (value "22nF")
      (footprint "eagle-import:0805")
      (libsource (lib "eagle-import") (part "CAP0805"))
    )
    (comp (ref "C28")
      (value "22uF")
      (footprint "eagle-import:0805")
      (libsource (lib "eagle-import") (part "CAP0805"))
    )
    (comp (ref "C29")
      (value "150nF")
      (footprint "eagle-import:0805")
      (libsource (lib "eagle-import") (part "CAP0805"))
    )
    (comp (ref "C30")
      (value "10nF")
      (footprint "eagle-import:0805")
      (libsource (lib "eagle-import") (part "CAP0805"))
    )
    (comp (ref "C31")
      (value "10nF")
      (footprint "eagle-import:0805")
      (libsource (lib "eagle-import") (part "CAP0805"))
    )
    (comp (ref "D4")
      (value "SMBJ5343B")
      (footprint "eagle-import:DO214AA")
      (libsource (lib "eagle-import") (part "SMBJ5343B"))
    )
    (comp (ref "F3")
      (value "2016L500")
      (footprint "eagle-import:2016")
      (libsource (lib "eagle-import") (part "2016L500"))
    )
    (comp (ref "F4")
      (value "2016L500")
      (footprint "eagle-import:2016")
      (libsource (lib "eagle-import") (part "2016L500"))
    )
    (comp (ref "L3")
      (value "56uH")
      (footprint "eagle-import:1812")
      (libsource (lib "eagle-import") (part "IND1812"))
    )
    (comp (ref "LIFEPO41")
      (value "~3.5V")
      (footprint "eagle-import:EQUISAT-BATTERY-VA")
      (libsource (lib "eagle-import") (part "LIFEPO4VA"))
    )
    (comp (ref "LIFEPO42")
      (value "~3.5V")
      (footprint "eagle-import:EQUISAT-BATTERY-VB")
      (libsource (lib "eagle-import") (part "LIFEPO4VB"))
    )
    (comp (ref "R24")
      (value "220K")
      (footprint "eagle-import:0805")
      (libsource (lib "eagle-import") (part "RES0805"))
    )
    (comp (ref "R26")
      (value "100K")
      (footprint "eagle-import:0805")
      (libsource (lib "eagle-import") (part "RES0805"))
    )
    (comp (ref "R41")
      (value "0.001R@1W")
      (footprint "eagle-import:1210")
      (libsource (lib "eagle-import") (part "RES1210"))
    )
    (comp (ref "R42")
      (value "470K")
      (footprint "eagle-import:0805")
      (libsource (lib "eagle-import") (part "RES0805"))
    )
    (comp (ref "R43")
      (value "470K")
      (footprint "eagle-import:0805")
      (libsource (lib "eagle-import") (part "RES0805"))
    )
    (comp (ref "R44")
      (value "100K")
      (footprint "eagle-import:0805")
      (libsource (lib "eagle-import") (part "RES0805"))
    )
    (comp (ref "R45")
      (value "330K")
      (footprint "eagle-import:0805")
      (libsource (lib "eagle-import") (part "RES0805"))
    )
    (comp (ref "R46")
      (value "43K")
      (footprint "eagle-import:0805")
      (libsource (lib "eagle-import") (part "RES0805"))
    )
    (comp (ref "R47")
      (value "95K")
      (footprint "eagle-import:0805")
      (libsource (lib "eagle-import") (part "RES0805"))
    )
    (comp (ref "R48")
      (value "100K")
      (footprint "eagle-import:0805")
      (libsource (lib "eagle-import") (part "RES0805"))
    )
    (comp (ref "R49")
      (value "287K")
      (footprint "eagle-import:0805")
      (libsource (lib "eagle-import") (part "RES0805"))
    )
    (comp (ref "R50")
      (value "100K")
      (footprint "eagle-import:0805")
      (libsource (lib "eagle-import") (part "RES0805"))
    )
    (comp (ref "R51")
      (value "6.04K")
      (footprint "eagle-import:0805")
      (libsource (lib "eagle-import") (part "RES0805"))
    )
    (comp (ref "R52")
      (value "887K")
      (footprint "eagle-import:0805")
      (libsource (lib "eagle-import") (part "RES0805"))
    )
    (comp (ref "R53")
      (value "1.74M")
      (footprint "eagle-import:0805")
      (libsource (lib "eagle-import") (part "RES0805"))
    )
    (comp (ref "R54")
      (value "34.8R@1W")
      (footprint "eagle-import:1210")
      (libsource (lib "eagle-import") (part "RES1210"))
    )
    (comp (ref "R55")
      (value "34.8R@1W")
      (footprint "eagle-import:1210")
      (libsource (lib "eagle-import") (part "RES1210"))
    )
    (comp (ref "R56")
      (value "100K")
      (footprint "eagle-import:0805")
      (libsource (lib "eagle-import") (part "RES0805"))
    )
    (comp (ref "R57")
      (value "100K")
      (footprint "eagle-import:0805")
      (libsource (lib "eagle-import") (part "RES0805"))
    )
    (comp (ref "R58")
      (value "1K")
      (footprint "eagle-import:0805")
      (libsource (lib "eagle-import") (part "RES0805"))
    )
    (comp (ref "R77")
      (value "100K")
      (footprint "eagle-import:0805")
      (libsource (lib "eagle-import") (part "RES0805"))
    )
    (comp (ref "R78")
      (value "4.7K")
      (footprint "eagle-import:0805")
      (libsource (lib "eagle-import") (part "RES0805"))
    )
    (comp (ref "R79")
      (value "4.7K")
      (footprint "eagle-import:0805")
      (libsource (lib "eagle-import") (part "RES0805"))
    )
    (comp (ref "SW1")
      (value "BTS50015-1TAD")
      (footprint "eagle-import:TO-263-7-8")
      (libsource (lib "eagle-import") (part "BTS50015-1TAD"))
    )
    (comp (ref "U14")
      (value "LTC4121")
      (footprint "eagle-import:QFN-16-PAD")
      (libsource (lib "eagle-import") (part "LTC4121"))
    )
    (comp (ref "U15")
      (value "VNS3NV04DP-E")
      (footprint "eagle-import:SO-8")
      (libsource (lib "eagle-import") (part "VNS3NV04DP-E"))
    )
    (comp (ref "U18")
      (value "AD8418")
      (footprint "eagle-import:MSOP-8")
      (libsource (lib "eagle-import") (part "AD8418"))
    )
    (comp (ref "V32")
      (value "LFB1_CHG")
      (footprint "eagle-import:VIA-60MIL-SQ")
      (libsource (lib "eagle-import") (part "VIA60MIL-SQ"))
    )
    (comp (ref "V35")
      (value "LFB1_CHG")
      (footprint "eagle-import:VIA-60MIL")
      (libsource (lib "eagle-import") (part "VIA-60MIL"))
    )
    (comp (ref "V40")
      (value "LFB1SNS")
      (footprint "eagle-import:VIA-60MIL")
      (libsource (lib "eagle-import") (part "VIA-60MIL"))
    )
    (comp (ref "V41")
      (value "LF1_REF")
      (footprint "eagle-import:VIA-60MIL")
      (libsource (lib "eagle-import") (part "VIA-60MIL"))
    )
    (comp (ref "V42")
      (value "LF2_REF")
      (footprint "eagle-import:VIA-60MIL")
      (libsource (lib "eagle-import") (part "VIA-60MIL"))
    )
    (comp (ref "V43")
      (value "LFB1_OUTEN")
      (footprint "eagle-import:VIA-60MIL")
      (libsource (lib "eagle-import") (part "VIA-60MIL"))
    )
    (comp (ref "V45")
      (value "LF_B1")
      (footprint "eagle-import:VIA-120MIL")
      (libsource (lib "eagle-import") (part "VIA-120MIL"))
    )
    (comp (ref "V46")
      (value "LFB1_OSNS")
      (footprint "eagle-import:VIA-60MIL")
      (libsource (lib "eagle-import") (part "VIA-60MIL"))
    )
  )
  (nets
    (net (code "1") (name "+3V3") (class "Default")
      (node (ref "C1") (pin "1") (pinfunction "P$1_1") (pintype "passive"))
      (node (ref "C2") (pin "1") (pinfunction "P$1_1") (pintype "passive"))
      (node (ref "R17") (pin "2") (pinfunction "2_2") (pintype "passive"))
      (node (ref "R18") (pin "2") (pinfunction "2_2") (pintype "passive"))
      (node (ref "R2") (pin "2") (pinfunction "2_2") (pintype "passive"))
      (node (ref "R20") (pin "1") (pinfunction "1_1") (pintype "passive"))
      (node (ref "R24") (pin "1") (pinfunction "1_1") (pintype "passive"))
      (node (ref "R29") (pin "1") (pinfunction "1_1") (pintype "passive"))
      (node (ref "R3") (pin "2") (pinfunction "2_2") (pintype "passive"))
      (node (ref "R4") (pin "1") (pinfunction "1_1") (pintype "passive"))
      (node (ref "R42") (pin "2") (pinfunction "2_2") (pintype "passive"))
      (node (ref "R43") (pin "2") (pinfunction "2_2") (pintype "passive"))
      (node (ref "R60") (pin "2") (pinfunction "2_2") (pintype "passive"))
      (node (ref "R61") (pin "2") (pinfunction "2_2") (pintype "passive"))
      (node (ref "R83") (pin "2") (pinfunction "2_2") (pintype "passive"))
      (node (ref "R84") (pin "2") (pinfunction "2_2") (pintype "passive"))
      (node (ref "R85") (pin "2") (pinfunction "2_2") (pintype "passive"))
      (node (ref "R86") (pin "2") (pinfunction "2_2") (pintype "passive"))
      (node (ref "U1") (pin "P$24") (pinfunction "VCC_P$24") (pintype "power_in"))
      (node (ref "U18") (pin "P$6") (pinfunction "VS_P$6") (pintype "bidirectional"))
      (node (ref "U19") (pin "P$6") (pinfunction "VS_P$6") (pintype "bidirectional"))
      (node (ref "U2") (pin "P$8") (pinfunction "VDD_P$8") (pintype "bidirectional"))
      (node (ref "U8") (pin "P$6") (pinfunction "VS_P$6") (pintype "bidirectional"))
      (node (ref "U9") (pin "P$6") (pinfunction "VS_P$6") (pintype "bidirectional"))
      (node (ref "V12") (pin "P$1") (pinfunction "P$1_P$1") (pintype "bidirectional"))
    )
    (net (code "2") (name "5V") (class "Default")
      (node (ref "T1") (pin "+") (pinfunction "+_+") (pintype "bidirectional"))
      (node (ref "T2") (pin "+") (pinfunction "+_+") (pintype "bidirectional"))
      (node (ref "T3") (pin "+") (pinfunction "+_+") (pintype "bidirectional"))
      (node (ref "T4") (pin "+") (pinfunction "+_+") (pintype "bidirectional"))
      (node (ref "V7") (pin "P$1") (pinfunction "P$1_P$1") (pintype "bidirectional"))
    )
    (net (code "3") (name "GND") (class "Default")
      (node (ref "C1") (pin "2") (pinfunction "P$2_2") (pintype "passive"))
      (node (ref "C11") (pin "2") (pinfunction "P$2_2") (pintype "passive"))
      (node (ref "C12") (pin "2") (pinfunction "P$2_2") (pintype "passive"))
      (node (ref "C13") (pin "1") (pinfunction "P$1_1") (pintype "passive"))
      (node (ref "C14") (pin "1") (pinfunction "P$1_1") (pintype "passive"))
      (node (ref "C15") (pin "1") (pinfunction "P$1_1") (pintype "passive"))
      (node (ref "C16") (pin "1") (pinfunction "P$1_1") (pintype "passive"))
      (node (ref "C17") (pin "2") (pinfunction "P$2_2") (pintype "passive"))
      (node (ref "C18") (pin "2") (pinfunction "P$2_2") (pintype "passive"))
      (node (ref "C2") (pin "2") (pinfunction "P$2_2") (pintype "passive"))
      (node (ref "C21") (pin "2") (pinfunction "P$2_2") (pintype "passive"))
      (node (ref "C22") (pin "2") (pinfunction "P$2_2") (pintype "passive"))
      (node (ref "C23") (pin "2") (pinfunction "P$2_2") (pintype "passive"))
      (node (ref "C24") (pin "2") (pinfunction "P$2_2") (pintype "passive"))
      (node (ref "C25") (pin "1") (pinfunction "P$1_1") (pintype "passive"))
      (node (ref "C26") (pin "1") (pinfunction "P$1_1") (pintype "passive"))
      (node (ref "C28") (pin "2") (pinfunction "P$2_2") (pintype "passive"))
      (node (ref "C29") (pin "1") (pinfunction "P$1_1") (pintype "passive"))
      (node (ref "C3") (pin "2") (pinfunction "P$2_2") (pintype "passive"))
      (node (ref "C30") (pin "2") (pinfunction "P$2_2") (pintype "passive"))
      (node (ref "C31") (pin "2") (pinfunction "P$2_2") (pintype "passive"))
      (node (ref "C32") (pin "1") (pinfunction "P$1_1") (pintype "passive"))
      (node (ref "C33") (pin "1") (pinfunction "P$1_1") (pintype "passive"))
      (node (ref "C35") (pin "2") (pinfunction "P$2_2") (pintype "passive"))
      (node (ref "C36") (pin "1") (pinfunction "P$1_1") (pintype "passive"))
      (node (ref "C37") (pin "2") (pinfunction "P$2_2") (pintype "passive"))
      (node (ref "C38") (pin "2") (pinfunction "P$2_2") (pintype "passive"))
      (node (ref "C4") (pin "2") (pinfunction "P$2_2") (pintype "passive"))
      (node (ref "C5") (pin "2") (pinfunction "P$2_2") (pintype "passive"))
      (node (ref "C6") (pin "2") (pinfunction "P$2_2") (pintype "passive"))
      (node (ref "C7") (pin "2") (pinfunction "P$2_2") (pintype "passive"))
      (node (ref "C8") (pin "2") (pinfunction "P$2_2") (pintype "passive"))
      (node (ref "D4") (pin "A") (pinfunction "A_A") (pintype "passive"))
      (node (ref "D5") (pin "A") (pinfunction "A_A") (pintype "passive"))
      (node (ref "R11") (pin "1") (pinfunction "1_1") (pintype "passive"))
      (node (ref "R14") (pin "1") (pinfunction "1_1") (pintype "passive"))
      (node (ref "R19") (pin "1") (pinfunction "1_1") (pintype "passive"))
      (node (ref "R21") (pin "2") (pinfunction "2_2") (pintype "passive"))
      (node (ref "R23") (pin "1") (pinfunction "1_1") (pintype "passive"))
      (node (ref "R25") (pin "1") (pinfunction "1_1") (pintype "passive"))
      (node (ref "R26") (pin "2") (pinfunction "2_2") (pintype "passive"))
      (node (ref "R28") (pin "1") (pinfunction "1_1") (pintype "passive"))
      (node (ref "R30") (pin "2") (pinfunction "2_2") (pintype "passive"))
      (node (ref "R32") (pin "1") (pinfunction "1_1") (pintype "passive"))
      (node (ref "R34") (pin "1") (pinfunction "1_1") (pintype "passive"))
      (node (ref "R35") (pin "1") (pinfunction "1_1") (pintype "passive"))
      (node (ref "R36") (pin "1") (pinfunction "1_1") (pintype "passive"))
      (node (ref "R40") (pin "1") (pinfunction "1_1") (pintype "passive"))
      (node (ref "R41") (pin "P$1") (pinfunction "1_P$1") (pintype "passive"))
      (node (ref "R44") (pin "1") (pinfunction "1_1") (pintype "passive"))
      (node (ref "R46") (pin "1") (pinfunction "1_1") (pintype "passive"))
      (node (ref "R48") (pin "1") (pinfunction "1_1") (pintype "passive"))
      (node (ref "R50") (pin "1") (pinfunction "1_1") (pintype "passive"))
      (node (ref "R51") (pin "2") (pinfunction "2_2") (pintype "passive"))
      (node (ref "R56") (pin "1") (pinfunction "1_1") (pintype "passive"))
      (node (ref "R57") (pin "1") (pinfunction "1_1") (pintype "passive"))
      (node (ref "R58") (pin "1") (pinfunction "1_1") (pintype "passive"))
      (node (ref "R59") (pin "P$1") (pinfunction "1_P$1") (pintype "passive"))
      (node (ref "R6") (pin "2") (pinfunction "2_2") (pintype "passive"))
      (node (ref "R62") (pin "1") (pinfunction "1_1") (pintype "passive"))
      (node (ref "R64") (pin "1") (pinfunction "1_1") (pintype "passive"))
      (node (ref "R66") (pin "1") (pinfunction "1_1") (pintype "passive"))
      (node (ref "R68") (pin "1") (pinfunction "1_1") (pintype "passive"))
      (node (ref "R69") (pin "2") (pinfunction "2_2") (pintype "passive"))
      (node (ref "R74") (pin "1") (pinfunction "1_1") (pintype "passive"))
      (node (ref "R75") (pin "1") (pinfunction "1_1") (pintype "passive"))
      (node (ref "R76") (pin "1") (pinfunction "1_1") (pintype "passive"))
      (node (ref "R77") (pin "1") (pinfunction "1_1") (pintype "passive"))
      (node (ref "R8") (pin "1") (pinfunction "1_1") (pintype "passive"))
      (node (ref "R80") (pin "1") (pinfunction "1_1") (pintype "passive"))
      (node (ref "R9") (pin "1") (pinfunction "1_1") (pintype "passive"))
      (node (ref "SW1") (pin "P$1") (pinfunction "GND_P$1") (pintype "bidirectional"))
      (node (ref "SW2") (pin "P$1") (pinfunction "GND_P$1") (pintype "bidirectional"))
      (node (ref "U1") (pin "P$12") (pinfunction "GND_P$12") (pintype "power_in"))
      (node (ref "U1") (pin "P$2") (pinfunction "A1_P$2") (pintype "bidirectional"))
      (node (ref "U1") (pin "P$21") (pinfunction "A0_P$21") (pintype "bidirectional"))
      (node (ref "U1") (pin "P$3") (pinfunction "A2_P$3") (pintype "bidirectional"))
      (node (ref "U10") (pin "P$4") (pinfunction "GND_P$4") (pintype "bidirectional"))
      (node (ref "U10") (pin "P$6") (pinfunction "NC_P$6") (pintype "bidirectional"))
      (node (ref "U10") (pin "P$7") (pinfunction "NC_P$7") (pintype "bidirectional"))
      (node (ref "U11") (pin "P$4") (pinfunction "GND_P$4") (pintype "bidirectional"))
      (node (ref "U11") (pin "P$6") (pinfunction "NC_P$6") (pintype "bidirectional"))
      (node (ref "U11") (pin "P$7") (pinfunction "NC_P$7") (pintype "bidirectional"))
      (node (ref "U12") (pin "P$2") (pinfunction "GND_P$2") (pintype "bidirectional"))
      (node (ref "U13") (pin "P$2") (pinfunction "GND_P$2") (pintype "bidirectional"))
      (node (ref "U14") (pin "P$12") (pinfunction "NTC_P$12") (pintype "bidirectional"))
      (node (ref "U14") (pin "P$17") (pinfunction "GND_P$17") (pintype "bidirectional"))
      (node (ref "U14") (pin "P$5") (pinfunction "GND_P$5") (pintype "bidirectional"))
      (node (ref "U14") (pin "P$7") (pinfunction "FREQ_P$7") (pintype "bidirectional"))
      (node (ref "U15") (pin "P$3") (pinfunction "S2_P$3") (pintype "bidirectional"))
      (node (ref "U16") (pin "P$12") (pinfunction "NTC_P$12") (pintype "bidirectional"))
      (node (ref "U16") (pin "P$17") (pinfunction "GND_P$17") (pintype "bidirectional"))
      (node (ref "U16") (pin "P$5") (pinfunction "GND_P$5") (pintype "bidirectional"))
      (node (ref "U16") (pin "P$7") (pinfunction "FREQ_P$7") (pintype "bidirectional"))
      (node (ref "U17") (pin "P$3") (pinfunction "S2_P$3") (pintype "bidirectional"))
      (node (ref "U18") (pin "P$1") (pinfunction "-IN_P$1") (pintype "bidirectional"))
      (node (ref "U18") (pin "P$2") (pinfunction "GND_P$2") (pintype "bidirectional"))
      (node (ref "U18") (pin "P$4") (pinfunction "NC_P$4") (pintype "bidirectional"))
      (node (ref "U19") (pin "P$1") (pinfunction "-IN_P$1") (pintype "bidirectional"))
      (node (ref "U19") (pin "P$2") (pinfunction "GND_P$2") (pintype "bidirectional"))
      (node (ref "U19") (pin "P$4") (pinfunction "NC_P$4") (pintype "bidirectional"))
      (node (ref "U2") (pin "P$7") (pinfunction "GND_P$7") (pintype "bidirectional"))
      (node (ref "U3") (pin "P$2") (pinfunction "GND_P$2") (pintype "bidirectional"))
      (node (ref "U3") (pin "P$3") (pinfunction "CNTL_P$3") (pintype "bidirectional"))
      (node (ref "U4") (pin "P$11") (pinfunction "NC_P$11") (pintype "bidirectional"))
      (node (ref "U4") (pin "P$12") (pinfunction "NTC_P$12") (pintype "bidirectional"))
      (node (ref "U4") (pin "P$17") (pinfunction "GND_P$17") (pintype "bidirectional"))
      (node (ref "U4") (pin "P$5") (pinfunction "GND_P$5") (pintype "bidirectional"))
      (node (ref "U4") (pin "P$7") (pinfunction "FREQ_P$7") (pintype "bidirectional"))
      (node (ref "U5") (pin "P$11") (pinfunction "NC_P$11") (pintype "bidirectional"))
      (node (ref "U5") (pin "P$12") (pinfunction "NTC_P$12") (pintype "bidirectional"))
      (node (ref "U5") (pin "P$17") (pinfunction "GND_P$17") (pintype "bidirectional"))
      (node (ref "U5") (pin "P$5") (pinfunction "GND_P$5") (pintype "bidirectional"))
      (node (ref "U5") (pin "P$7") (pinfunction "FREQ_P$7") (pintype "bidirectional"))
      (node (ref "U6") (pin "P$1") (pinfunction "S2_P$1") (pintype "bidirectional"))
      (node (ref "U6") (pin "P$3") (pinfunction "TST_P$3") (pintype "bidirectional"))
      (node (ref "U6") (pin "P$4") (pinfunction "VSS_P$4") (pintype "bidirectional"))
      (node (ref "U7") (pin "P$1") (pinfunction "S2_P$1") (pintype "bidirectional"))
      (node (ref "U7") (pin "P$3") (pinfunction "TST_P$3") (pintype "bidirectional"))
      (node (ref "U7") (pin "P$4") (pinfunction "VSS_P$4") (pintype "bidirectional"))
      (node (ref "U8") (pin "P$2") (pinfunction "GND_P$2") (pintype "bidirectional"))
      (node (ref "U8") (pin "P$4") (pinfunction "NC_P$4") (pintype "bidirectional"))
      (node (ref "U9") (pin "P$2") (pinfunction "GND_P$2") (pintype "bidirectional"))
      (node (ref "U9") (pin "P$4") (pinfunction "NC_P$4") (pintype "bidirectional"))
      (node (ref "V1") (pin "P$1") (pinfunction "P$1_P$1") (pintype "bidirectional"))
      (node (ref "V2") (pin "P$1") (pinfunction "P$1_P$1") (pintype "bidirectional"))
      (node (ref "V28") (pin "P$1") (pinfunction "P$1_P$1") (pintype "bidirectional"))
      (node (ref "V3") (pin "P$1") (pinfunction "P$1_P$1") (pintype "bidirectional"))
      (node (ref "V36") (pin "P$1") (pinfunction "P$1_P$1") (pintype "bidirectional"))
      (node (ref "V4") (pin "P$1") (pinfunction "P$1_P$1") (pintype "bidirectional"))
    )
    (net (code "4") (name "L1_CHG") (class "Default")
      (node (ref "R15") (pin "2") (pinfunction "2_2") (pintype "passive"))
      (node (ref "R35") (pin "2") (pinfunction "2_2") (pintype "passive"))
      (node (ref "U4") (pin "P$16") (pinfunction "RUN_P$16") (pintype "bidirectional"))
      (node (ref "V20") (pin "P$1") (pinfunction "P$1_P$1") (pintype "bidirectional"))
      (node (ref "V48") (pin "P$1") (pinfunction "P$1_P$1") (pintype "bidirectional"))
    )
    (net (code "5") (name "L1_CHGN") (class "Default")
      (node (ref "R17") (pin "1") (pinfunction "1_1") (pintype "passive"))
      (node (ref "U1") (pin "P$8") (pinfunction "P04_P$8") (pintype "bidirectional"))
      (node (ref "U4") (pin "P$14") (pinfunction "~{CHRG}_P$14") (pintype "bidirectional"))
      (node (ref "V27") (pin "P$1") (pinfunction "P$1_P$1") (pintype "bidirectional"))
    )
    (net (code "6") (name "L1_DISG") (class "Default")
      (node (ref "U12") (pin "P$3") (pinfunction "CNTRL_P$3") (pintype "bidirectional"))
      (node (ref "V29") (pin "P$1") (pinfunction "P$1_P$1") (pintype "bidirectional"))
    )
    (net (code "7") (name "L1_FAULTN") (class "Default")
      (node (ref "R18") (pin "1") (pinfunction "1_1") (pintype "passive"))
      (node (ref "U1") (pin "P$9") (pinfunction "P05_P$9") (pintype "bidirectional"))
      (node (ref "U4") (pin "P$15") (pinfunction "~{FAULT}_P$15") (pintype "bidirectional"))
      (node (ref "V26") (pin "P$1") (pinfunction "P$1_P$1") (pintype "bidirectional"))
    )
    (net (code "8") (name "L1_PROG") (class "Default")
      (node (ref "R25") (pin "2") (pinfunction "2_2") (pintype "passive"))
      (node (ref "U4") (pin "P$13") (pinfunction "PROG_P$13") (pintype "bidirectional"))
    )
    (net (code "9") (name "L1_REF") (class "Default")
      (node (ref "R33") (pin "1") (pinfunction "1_1") (pintype "passive"))
      (node (ref "R34") (pin "2") (pinfunction "2_2") (pintype "passive"))
      (node (ref "V21") (pin "P$1") (pinfunction "P$1_P$1") (pintype "bidirectional"))
    )
    (net (code "10") (name "L1_SNS") (class "Default")
      (node (ref "U2") (pin "P$4") (pinfunction "VIN1_P$4") (pintype "bidirectional"))
      (node (ref "U8") (pin "P$5") (pinfunction "OUT_P$5") (pintype "bidirectional"))
    )
    (net (code "11") (name "L1_SNS+") (class "Default")
      (node (ref "LI-ION1") (pin "MINUS") (pinfunction "MINUS_MINUS") (pintype "power_in"))
      (node (ref "R31") (pin "P$2") (pinfunction "2_P$2") (pintype "passive"))
      (node (ref "U8") (pin "P$8") (pinfunction "+IN_P$8") (pintype "bidirectional"))
    )
    (net (code "12") (name "L1_SNS-") (class "Default")
      (node (ref "R31") (pin "P$1") (pinfunction "1_P$1") (pintype "passive"))
      (node (ref "U8") (pin "P$1") (pinfunction "-IN_P$1") (pintype "bidirectional"))
      (node (ref "V22") (pin "P$1") (pinfunction "P$1_P$1") (pintype "bidirectional"))
    )
    (net (code "13") (name "L1_ST") (class "Default")
      (node (ref "R37") (pin "1") (pinfunction "1_1") (pintype "passive"))
      (node (ref "U1") (pin "P$5") (pinfunction "P01_P$5") (pintype "bidirectional"))
      (node (ref "U12") (pin "P$4") (pinfunction "STAT_P$4") (pintype "bidirectional"))
    )
    (net (code "14") (name "L1_TEMP") (class "Default")
      (node (ref "T1") (pin "-") (pinfunction "-_-") (pintype "bidirectional"))
      (node (ref "V8") (pin "P$1") (pinfunction "P$1_P$1") (pintype "bidirectional"))
    )
    (net (code "15") (name "L2_CHG") (class "Default")
      (node (ref "R1") (pin "2") (pinfunction "2_2") (pintype "passive"))
      (node (ref "R36") (pin "2") (pinfunction "2_2") (pintype "passive"))
      (node (ref "U5") (pin "P$16") (pinfunction "RUN_P$16") (pintype "bidirectional"))
      (node (ref "V33") (pin "P$1") (pinfunction "P$1_P$1") (pintype "bidirectional"))
    )
    (net (code "16") (name "L2_CHGN") (class "Default")
      (node (ref "R2") (pin "1") (pinfunction "1_1") (pintype "passive"))
      (node (ref "U1") (pin "P$10") (pinfunction "P06_P$10") (pintype "bidirectional"))
      (node (ref "U5") (pin "P$14") (pinfunction "~{CHRG}_P$14") (pintype "bidirectional"))
    )
    (net (code "17") (name "L2_DISG") (class "Default")
      (node (ref "U13") (pin "P$3") (pinfunction "CNTRL_P$3") (pintype "bidirectional"))
      (node (ref "V30") (pin "P$1") (pinfunction "P$1_P$1") (pintype "bidirectional"))
    )
    (net (code "18") (name "L2_FAULTN") (class "Default")
      (node (ref "R3") (pin "1") (pinfunction "1_1") (pintype "passive"))
      (node (ref "U1") (pin "P$11") (pinfunction "P07_P$11") (pintype "bidirectional"))
      (node (ref "U5") (pin "P$15") (pinfunction "~{FAULT}_P$15") (pintype "bidirectional"))
    )
    (net (code "19") (name "L2_PROG") (class "Default")
      (node (ref "R9") (pin "2") (pinfunction "2_2") (pintype "passive"))
      (node (ref "U5") (pin "P$13") (pinfunction "PROG_P$13") (pintype "bidirectional"))
    )
    (net (code "20") (name "L2_REF") (class "Default")
      (node (ref "R16") (pin "1") (pinfunction "1_1") (pintype "passive"))
      (node (ref "R19") (pin "2") (pinfunction "2_2") (pintype "passive"))
      (node (ref "V31") (pin "P$1") (pinfunction "P$1_P$1") (pintype "bidirectional"))
    )
    (net (code "21") (name "L2_SNS") (class "Default")
      (node (ref "U2") (pin "P$3") (pinfunction "VIN0_P$3") (pintype "bidirectional"))
      (node (ref "U9") (pin "P$5") (pinfunction "OUT_P$5") (pintype "bidirectional"))
    )
    (net (code "22") (name "L2_SNS+") (class "Default")
      (node (ref "LI-ION2") (pin "MINUS") (pinfunction "MINUS_MINUS") (pintype "power_in"))
      (node (ref "R12") (pin "P$2") (pinfunction "2_P$2") (pintype "passive"))
      (node (ref "U9") (pin "P$8") (pinfunction "+IN_P$8") (pintype "bidirectional"))
    )
    (net (code "23") (name "L2_SNS-") (class "Default")
      (node (ref "R12") (pin "P$1") (pinfunction "1_P$1") (pintype "passive"))
      (node (ref "U9") (pin "P$1") (pinfunction "-IN_P$1") (pintype "bidirectional"))
      (node (ref "V24") (pin "P$1") (pinfunction "P$1_P$1") (pintype "bidirectional"))
    )
    (net (code "24") (name "L2_ST") (class "Default")
      (node (ref "R38") (pin "1") (pinfunction "1_1") (pintype "passive"))
      (node (ref "U1") (pin "P$4") (pinfunction "P00_P$4") (pintype "bidirectional"))
      (node (ref "U13") (pin "P$4") (pinfunction "STAT_P$4") (pintype "bidirectional"))
    )
    (net (code "25") (name "L2_TEMP") (class "Default")
      (node (ref "T2") (pin "-") (pinfunction "-_-") (pintype "bidirectional"))
      (node (ref "V9") (pin "P$1") (pinfunction "P$1_P$1") (pintype "bidirectional"))
    )
    (net (code "26") (name "LF1_REF") (class "Default")
      (node (ref "R49") (pin "2") (pinfunction "2_2") (pintype "passive"))
      (node (ref "R50") (pin "2") (pinfunction "2_2") (pintype "passive"))
      (node (ref "V41") (pin "P$1") (pinfunction "P$1_P$1") (pintype "bidirectional"))
    )
    (net (code "27") (name "LF1_TEMP") (class "Default")
      (node (ref "T3") (pin "-") (pinfunction "-_-") (pintype "bidirectional"))
      (node (ref "V10") (pin "P$1") (pinfunction "P$1_P$1") (pintype "bidirectional"))
    )
    (net (code "28") (name "LF2_REF") (class "Default")
      (node (ref "R47") (pin "1") (pinfunction "1_1") (pintype "passive"))
      (node (ref "R48") (pin "2") (pinfunction "2_2") (pintype "passive"))
      (node (ref "V42") (pin "P$1") (pinfunction "P$1_P$1") (pintype "bidirectional"))
    )
    (net (code "29") (name "LF3_REF") (class "Default")
      (node (ref "R67") (pin "2") (pinfunction "2_2") (pintype "passive"))
      (node (ref "R68") (pin "2") (pinfunction "2_2") (pintype "passive"))
      (node (ref "V49") (pin "P$1") (pinfunction "P$1_P$1") (pintype "bidirectional"))
    )
    (net (code "30") (name "LF3_TEMP") (class "Default")
      (node (ref "T4") (pin "-") (pinfunction "-_-") (pintype "bidirectional"))
      (node (ref "V11") (pin "P$1") (pinfunction "P$1_P$1") (pintype "bidirectional"))
    )
    (net (code "31") (name "LF4_REF") (class "Default")
      (node (ref "R65") (pin "1") (pinfunction "1_1") (pintype "passive"))
      (node (ref "R66") (pin "2") (pinfunction "2_2") (pintype "passive"))
      (node (ref "V50") (pin "P$1") (pinfunction "P$1_P$1") (pintype "bidirectional"))
    )
    (net (code "32") (name "LFB1_SNS+") (class "Default")
      (node (ref "LIFEPO42") (pin "MINUS") (pinfunction "MINUS_MINUS") (pintype "power_in"))
      (node (ref "R41") (pin "P$2") (pinfunction "2_P$2") (pintype "passive"))
      (node (ref "U18") (pin "P$8") (pinfunction "+IN_P$8") (pintype "bidirectional"))
    )
    (net (code "33") (name "LFB2_SNS+") (class "Default")
      (node (ref "LIFEPO44") (pin "MINUS") (pinfunction "MINUS_MINUS") (pintype "power_in"))
      (node (ref "R59") (pin "P$2") (pinfunction "2_P$2") (pintype "passive"))
      (node (ref "U19") (pin "P$8") (pinfunction "+IN_P$8") (pintype "bidirectional"))
    )
    (net (code "34") (name "LF_B1") (class "Default")
      (node (ref "C30") (pin "1") (pinfunction "P$1_1") (pintype "passive"))
      (node (ref "SW1") (pin "P$5") (pinfunction "OUT_P$5") (pintype "power_in"))
      (node (ref "SW1") (pin "P$6") (pinfunction "OUT_P$6") (pintype "power_in"))
      (node (ref "SW1") (pin "P$7") (pinfunction "OUT_P$7") (pintype "power_in"))
      (node (ref "V45") (pin "P$1") (pinfunction "P$1_P$1") (pintype "bidirectional"))
    )
    (net (code "35") (name "LF_B1_BT") (class "Default")
      (node (ref "R57") (pin "2") (pinfunction "2_2") (pintype "passive"))
      (node (ref "U1") (pin "P$16") (pinfunction "P13_P$16") (pintype "bidirectional"))
      (node (ref "U15") (pin "P$4") (pinfunction "G2_P$4") (pintype "bidirectional"))
    )
    (net (code "36") (name "LF_B1_CHG") (class "Default")
      (node (ref "R44") (pin "2") (pinfunction "2_2") (pintype "passive"))
      (node (ref "U14") (pin "P$16") (pinfunction "RUN_P$16") (pintype "bidirectional"))
      (node (ref "V32") (pin "P$1") (pinfunction "P$1_P$1") (pintype "bidirectional"))
      (node (ref "V35") (pin "P$1") (pinfunction "P$1_P$1") (pintype "bidirectional"))
    )
    (net (code "37") (name "LF_B1_CHGN") (class "Default")
      (node (ref "R42") (pin "1") (pinfunction "1_1") (pintype "passive"))
      (node (ref "U1") (pin "P$20") (pinfunction "P17_P$20") (pintype "bidirectional"))
      (node (ref "U14") (pin "P$14") (pinfunction "~{CHRG}_P$14") (pintype "bidirectional"))
    )
    (net (code "38") (name "LF_B1_FAULTN") (class "Default")
      (node (ref "R43") (pin "1") (pinfunction "1_1") (pintype "passive"))
      (node (ref "U1") (pin "P$19") (pinfunction "P16_P$19") (pintype "bidirectional"))
      (node (ref "U14") (pin "P$15") (pinfunction "~{FAULT}_P$15") (pintype "bidirectional"))
    )
    (net (code "39") (name "LF_B1_OSNS") (class "Default")
      (node (ref "C31") (pin "1") (pinfunction "P$1_1") (pintype "passive"))
      (node (ref "R79") (pin "1") (pinfunction "1_1") (pintype "passive"))
      (node (ref "V46") (pin "P$1") (pinfunction "P$1_P$1") (pintype "bidirectional"))
    )
    (net (code "40") (name "LF_B1_OUTEN") (class "Default")
      (node (ref "R78") (pin "1") (pinfunction "1_1") (pintype "passive"))
      (node (ref "V43") (pin "P$1") (pinfunction "P$1_P$1") (pintype "bidirectional"))
    )
    (net (code "41") (name "LF_B1_SNS") (class "Default")
      (node (ref "U18") (pin "P$5") (pinfunction "OUT_P$5") (pintype "bidirectional"))
      (node (ref "V40") (pin "P$1") (pinfunction "P$1_P$1") (pintype "bidirectional"))
    )
    (net (code "42") (name "LF_B1_TT") (class "Default")
      (node (ref "R56") (pin "2") (pinfunction "2_2") (pintype "passive"))
      (node (ref "U1") (pin "P$15") (pinfunction "P12_P$15") (pintype "bidirectional"))
      (node (ref "U15") (pin "P$2") (pinfunction "G1_P$2") (pintype "bidirectional"))
    )
    (net (code "43") (name "LF_B2") (class "Default")
      (node (ref "C37") (pin "1") (pinfunction "P$1_1") (pintype "passive"))
      (node (ref "SW2") (pin "P$5") (pinfunction "OUT_P$5") (pintype "power_in"))
      (node (ref "SW2") (pin "P$6") (pinfunction "OUT_P$6") (pintype "power_in"))
      (node (ref "SW2") (pin "P$7") (pinfunction "OUT_P$7") (pintype "power_in"))
      (node (ref "V53") (pin "P$1") (pinfunction "P$1_P$1") (pintype "bidirectional"))
    )
    (net (code "44") (name "LF_B2_BT") (class "Default")
      (node (ref "R75") (pin "2") (pinfunction "2_2") (pintype "passive"))
      (node (ref "U1") (pin "P$13") (pinfunction "P10_P$13") (pintype "bidirectional"))
      (node (ref "U17") (pin "P$4") (pinfunction "G2_P$4") (pintype "bidirectional"))
    )
    (net (code "45") (name "LF_B2_CHG") (class "Default")
      (node (ref "R62") (pin "2") (pinfunction "2_2") (pintype "passive"))
      (node (ref "U16") (pin "P$16") (pinfunction "RUN_P$16") (pintype "bidirectional"))
      (node (ref "V47") (pin "P$1") (pinfunction "P$1_P$1") (pintype "bidirectional"))
    )
    (net (code "46") (name "LF_B2_CHGN") (class "Default")
      (node (ref "R60") (pin "1") (pinfunction "1_1") (pintype "passive"))
      (node (ref "U1") (pin "P$17") (pinfunction "P14_P$17") (pintype "bidirectional"))
      (node (ref "U16") (pin "P$14") (pinfunction "~{CHRG}_P$14") (pintype "bidirectional"))
    )
    (net (code "47") (name "LF_B2_FAULTN") (class "Default")
      (node (ref "R61") (pin "1") (pinfunction "1_1") (pintype "passive"))
      (node (ref "U1") (pin "P$18") (pinfunction "P15_P$18") (pintype "bidirectional"))
      (node (ref "U16") (pin "P$15") (pinfunction "~{FAULT}_P$15") (pintype "bidirectional"))
    )
    (net (code "48") (name "LF_B2_OSNS") (class "Default")
      (node (ref "C38") (pin "1") (pinfunction "P$1_1") (pintype "passive"))
      (node (ref "R82") (pin "1") (pinfunction "1_1") (pintype "passive"))
      (node (ref "V99") (pin "P$1") (pinfunction "P$1_P$1") (pintype "bidirectional"))
    )
    (net (code "49") (name "LF_B2_OUTEN") (class "Default")
      (node (ref "R81") (pin "1") (pinfunction "1_1") (pintype "passive"))
      (node (ref "V51") (pin "P$1") (pinfunction "P$1_P$1") (pintype "bidirectional"))
    )
    (net (code "50") (name "LF_B2_SNS") (class "Default")
      (node (ref "U19") (pin "P$5") (pinfunction "OUT_P$5") (pintype "bidirectional"))
      (node (ref "V44") (pin "P$1") (pinfunction "P$1_P$1") (pintype "bidirectional"))
    )
    (net (code "51") (name "LF_B2_TT") (class "Default")
      (node (ref "R74") (pin "2") (pinfunction "2_2") (pintype "passive"))
      (node (ref "U1") (pin "P$14") (pinfunction "P11_P$14") (pintype "bidirectional"))
      (node (ref "U17") (pin "P$2") (pinfunction "G1_P$2") (pintype "bidirectional"))
    )
    (net (code "52") (name "LIFE1") (class "Default")
      (node (ref "C28") (pin "1") (pinfunction "P$1_1") (pintype "passive"))
      (node (ref "D4") (pin "C") (pinfunction "C_C") (pintype "passive"))
      (node (ref "F3") (pin "P$1") (pinfunction "P$1_P$1") (pintype "passive"))
      (node (ref "F4") (pin "P$1") (pinfunction "P$1_P$1") (pintype "passive"))
      (node (ref "LIFEPO41") (pin "PLUS") (pinfunction "PLUS_PLUS") (pintype "power_in"))
      (node (ref "R49") (pin "1") (pinfunction "1_1") (pintype "passive"))
      (node (ref "R53") (pin "2") (pinfunction "2_2") (pintype "passive"))
      (node (ref "R54") (pin "P$2") (pinfunction "2_P$2") (pintype "passive"))
      (node (ref "U14") (pin "P$9") (pinfunction "BAT_P$9") (pintype "bidirectional"))
    )
    (net (code "53") (name "LIFE1FUSEOUT") (class "Default")
      (node (ref "F3") (pin "P$2") (pinfunction "P$2_P$2") (pintype "passive"))
      (node (ref "F4") (pin "P$2") (pinfunction "P$2_P$2") (pintype "passive"))
      (node (ref "SW1") (pin "PAD") (pinfunction "VB_PAD") (pintype "power_in"))
    )
    (net (code "54") (name "LIFE3") (class "Default")
      (node (ref "C35") (pin "1") (pinfunction "P$1_1") (pintype "passive"))
      (node (ref "D5") (pin "C") (pinfunction "C_C") (pintype "passive"))
      (node (ref "F5") (pin "P$1") (pinfunction "P$1_P$1") (pintype "passive"))
      (node (ref "F6") (pin "P$1") (pinfunction "P$1_P$1") (pintype "passive"))
      (node (ref "LIFEPO43") (pin "PLUS") (pinfunction "PLUS_PLUS") (pintype "power_in"))
      (node (ref "R67") (pin "1") (pinfunction "1_1") (pintype "passive"))
      (node (ref "R71") (pin "2") (pinfunction "2_2") (pintype "passive"))
      (node (ref "R72") (pin "P$2") (pinfunction "2_P$2") (pintype "passive"))
      (node (ref "U16") (pin "P$9") (pinfunction "BAT_P$9") (pintype "bidirectional"))
    )
    (net (code "55") (name "LIFE3FUSEOUT") (class "Default")
      (node (ref "F5") (pin "P$2") (pinfunction "P$2_P$2") (pintype "passive"))
      (node (ref "F6") (pin "P$2") (pinfunction "P$2_P$2") (pintype "passive"))
      (node (ref "SW2") (pin "PAD") (pinfunction "VB_PAD") (pintype "power_in"))
    )
    (net (code "56") (name "LION1") (class "Default")
      (node (ref "C11") (pin "1") (pinfunction "P$1_1") (pintype "passive"))
      (node (ref "F1") (pin "1") (pinfunction "P$1_1") (pintype "passive"))
      (node (ref "LI-ION1") (pin "PLUS") (pinfunction "PLUS_PLUS") (pintype "power_in"))
      (node (ref "R33") (pin "2") (pinfunction "2_2") (pintype "passive"))
      (node (ref "R7") (pin "2") (pinfunction "2_2") (pintype "passive"))
      (node (ref "U4") (pin "P$10") (pinfunction "BATSNS_P$10") (pintype "bidirectional"))
      (node (ref "U4") (pin "P$9") (pinfunction "BAT_P$9") (pintype "bidirectional"))
    )
    (net (code "57") (name "LION1_OUT") (class "Default")
      (node (ref "C15") (pin "2") (pinfunction "P$2_2") (pintype "passive"))
      (node (ref "F1") (pin "2") (pinfunction "P$2_2") (pintype "passive"))
      (node (ref "U12") (pin "P$1") (pinfunction "IN_P$1") (pintype "bidirectional"))
    )
    (net (code "58") (name "LION2") (class "Default")
      (node (ref "C12") (pin "1") (pinfunction "P$1_1") (pintype "passive"))
      (node (ref "F2") (pin "1") (pinfunction "P$1_1") (pintype "passive"))
      (node (ref "LI-ION2") (pin "PLUS") (pinfunction "PLUS_PLUS") (pintype "power_in"))
      (node (ref "R16") (pin "2") (pinfunction "2_2") (pintype "passive"))
      (node (ref "R22") (pin "2") (pinfunction "2_2") (pintype "passive"))
      (node (ref "U5") (pin "P$10") (pinfunction "BATSNS_P$10") (pintype "bidirectional"))
      (node (ref "U5") (pin "P$9") (pinfunction "BAT_P$9") (pintype "bidirectional"))
    )
    (net (code "59") (name "LION2_OUT") (class "Default")
      (node (ref "C16") (pin "2") (pinfunction "P$2_2") (pintype "passive"))
      (node (ref "F2") (pin "2") (pinfunction "P$2_2") (pintype "passive"))
      (node (ref "U13") (pin "P$1") (pinfunction "IN_P$1") (pintype "bidirectional"))
    )
    (net (code "60") (name "L_OUT") (class "Default")
      (node (ref "C21") (pin "1") (pinfunction "P$1_1") (pintype "passive"))
      (node (ref "C22") (pin "1") (pinfunction "P$1_1") (pintype "passive"))
      (node (ref "D2") (pin "C") (pinfunction "C_C") (pintype "bidirectional"))
      (node (ref "D3") (pin "C") (pinfunction "C_C") (pintype "bidirectional"))
      (node (ref "R37") (pin "2") (pinfunction "2_2") (pintype "passive"))
      (node (ref "R38") (pin "2") (pinfunction "2_2") (pintype "passive"))
      (node (ref "R39") (pin "2") (pinfunction "2_2") (pintype "passive"))
      (node (ref "U12") (pin "P$5") (pinfunction "OUT_P$5") (pintype "bidirectional"))
      (node (ref "U13") (pin "P$5") (pinfunction "OUT_P$5") (pintype "bidirectional"))
      (node (ref "V34") (pin "P$1") (pinfunction "P$1_P$1") (pintype "bidirectional"))
    )
    (net (code "61") (name "L_REF") (class "Default")
      (node (ref "R39") (pin "1") (pinfunction "1_1") (pintype "passive"))
      (node (ref "R40") (pin "2") (pinfunction "2_2") (pintype "passive"))
      (node (ref "U2") (pin "P$5") (pinfunction "VIN2_P$5") (pintype "bidirectional"))
    )
    (net (code "62") (name "Net-(C7-P$1)") (class "Default")
      (node (ref "C7") (pin "1") (pinfunction "P$1_1") (pintype "passive"))
      (node (ref "U4") (pin "P$1") (pinfunction "INTVCC_P$1") (pintype "bidirectional"))
    )
    (net (code "63") (name "Net-(C8-P$1)") (class "Default")
      (node (ref "C8") (pin "1") (pinfunction "P$1_1") (pintype "passive"))
      (node (ref "U5") (pin "P$1") (pinfunction "INTVCC_P$1") (pintype "bidirectional"))
    )
    (net (code "64") (name "Net-(C9-P$1)") (class "Default")
      (node (ref "C9") (pin "1") (pinfunction "P$1_1") (pintype "passive"))
      (node (ref "U4") (pin "P$2") (pinfunction "BOOST_P$2") (pintype "bidirectional"))
    )
    (net (code "65") (name "Net-(C9-P$2)") (class "Default")
      (node (ref "C9") (pin "2") (pinfunction "P$2_2") (pintype "passive"))
      (node (ref "L1") (pin "P$1") (pinfunction "P$1_P$1") (pintype "passive"))
      (node (ref "U4") (pin "P$4") (pinfunction "SW_P$4") (pintype "bidirectional"))
    )
    (net (code "66") (name "Net-(C10-P$1)") (class "Default")
      (node (ref "C10") (pin "1") (pinfunction "P$1_1") (pintype "passive"))
      (node (ref "U5") (pin "P$2") (pinfunction "BOOST_P$2") (pintype "bidirectional"))
    )
    (net (code "67") (name "Net-(C10-P$2)") (class "Default")
      (node (ref "C10") (pin "2") (pinfunction "P$2_2") (pintype "passive"))
      (node (ref "L2") (pin "P$1") (pinfunction "P$1_P$1") (pintype "passive"))
      (node (ref "U5") (pin "P$4") (pinfunction "SW_P$4") (pintype "bidirectional"))
    )
    (net (code "68") (name "Net-(C13-P$2)") (class "Default")
      (node (ref "C13") (pin "2") (pinfunction "P$2_2") (pintype "passive"))
      (node (ref "R7") (pin "1") (pinfunction "1_1") (pintype "passive"))
      (node (ref "U6") (pin "P$5") (pinfunction "VCC_P$5") (pintype "bidirectional"))
    )
    (net (code "69") (name "Net-(C14-P$2)") (class "Default")
      (node (ref "C14") (pin "2") (pinfunction "P$2_2") (pintype "passive"))
      (node (ref "R22") (pin "1") (pinfunction "1_1") (pintype "passive"))
      (node (ref "U7") (pin "P$5") (pinfunction "VCC_P$5") (pintype "bidirectional"))
    )
    (net (code "70") (name "Net-(C19-P$1)") (class "Default")
      (node (ref "C19") (pin "1") (pinfunction "P$1_1") (pintype "passive"))
      (node (ref "C23") (pin "1") (pinfunction "P$1_1") (pintype "passive"))
      (node (ref "D2") (pin "A") (pinfunction "A_A") (pintype "bidirectional"))
      (node (ref "U10") (pin "P$1") (pinfunction "OUT_P$1") (pintype "bidirectional"))
      (node (ref "U10") (pin "P$2") (pinfunction "SENSE_P$2") (pintype "bidirectional"))
    )
    (net (code "71") (name "Net-(C19-P$2)") (class "Default")
      (node (ref "C19") (pin "2") (pinfunction "P$2_2") (pintype "passive"))
      (node (ref "U10") (pin "P$3") (pinfunction "BYP_P$3") (pintype "bidirectional"))
    )
    (net (code "72") (name "Net-(C20-P$1)") (class "Default")
      (node (ref "C20") (pin "1") (pinfunction "P$1_1") (pintype "passive"))
      (node (ref "C24") (pin "1") (pinfunction "P$1_1") (pintype "passive"))
      (node (ref "D3") (pin "A") (pinfunction "A_A") (pintype "bidirectional"))
      (node (ref "U11") (pin "P$1") (pinfunction "OUT_P$1") (pintype "bidirectional"))
      (node (ref "U11") (pin "P$2") (pinfunction "SENSE_P$2") (pintype "bidirectional"))
    )
    (net (code "73") (name "Net-(C20-P$2)") (class "Default")
      (node (ref "C20") (pin "2") (pinfunction "P$2_2") (pintype "passive"))
      (node (ref "U11") (pin "P$3") (pinfunction "BYP_P$3") (pintype "bidirectional"))
    )
    (net (code "74") (name "Net-(C26-P$2)") (class "Default")
      (node (ref "C26") (pin "2") (pinfunction "P$2_2") (pintype "passive"))
      (node (ref "U14") (pin "P$1") (pinfunction "INTVCC_P$1") (pintype "bidirectional"))
    )
    (net (code "75") (name "Net-(C27-P$1)") (class "Default")
      (node (ref "C27") (pin "1") (pinfunction "P$1_1") (pintype "passive"))
      (node (ref "L3") (pin "P$2") (pinfunction "P$2_P$2") (pintype "passive"))
      (node (ref "U14") (pin "P$4") (pinfunction "SW_P$4") (pintype "bidirectional"))
    )
    (net (code "76") (name "Net-(C27-P$2)") (class "Default")
      (node (ref "C27") (pin "2") (pinfunction "P$2_2") (pintype "passive"))
      (node (ref "U14") (pin "P$2") (pinfunction "BOOST_P$2") (pintype "bidirectional"))
    )
    (net (code "77") (name "Net-(C29-P$2)") (class "Default")
      (node (ref "C29") (pin "2") (pinfunction "P$2_2") (pintype "passive"))
      (node (ref "R77") (pin "2") (pinfunction "2_2") (pintype "passive"))
      (node (ref "R78") (pin "2") (pinfunction "2_2") (pintype "passive"))
      (node (ref "SW1") (pin "P$2") (pinfunction "CNTRL_P$2") (pintype "input"))
    )
    (net (code "78") (name "Net-(C33-P$2)") (class "Default")
      (node (ref "C33") (pin "2") (pinfunction "P$2_2") (pintype "passive"))
      (node (ref "U16") (pin "P$1") (pinfunction "INTVCC_P$1") (pintype "bidirectional"))
    )
    (net (code "79") (name "Net-(C34-P$1)") (class "Default")
      (node (ref "C34") (pin "1") (pinfunction "P$1_1") (pintype "passive"))
      (node (ref "L4") (pin "P$2") (pinfunction "P$2_P$2") (pintype "passive"))
      (node (ref "U16") (pin "P$4") (pinfunction "SW_P$4") (pintype "bidirectional"))
    )
    (net (code "80") (name "Net-(C34-P$2)") (class "Default")
      (node (ref "C34") (pin "2") (pinfunction "P$2_2") (pintype "passive"))
      (node (ref "U16") (pin "P$2") (pinfunction "BOOST_P$2") (pintype "bidirectional"))
    )
    (net (code "81") (name "Net-(C36-P$2)") (class "Default")
      (node (ref "C36") (pin "2") (pinfunction "P$2_2") (pintype "passive"))
      (node (ref "R80") (pin "2") (pinfunction "2_2") (pintype "passive"))
      (node (ref "R81") (pin "2") (pinfunction "2_2") (pintype "passive"))
      (node (ref "SW2") (pin "P$2") (pinfunction "CNTRL_P$2") (pintype "input"))
    )
    (net (code "82") (name "Net-(M1-G)") (class "Default")
      (node (ref "M1") (pin "P$4") (pinfunction "G_P$4") (pintype "bidirectional"))
      (node (ref "U3") (pin "P$5") (pinfunction "GATE_P$5") (pintype "bidirectional"))
    )
    (net (code "83") (name "Net-(R54-1)") (class "Default")
      (node (ref "R54") (pin "P$1") (pinfunction "1_P$1") (pintype "passive"))
      (node (ref "U15") (pin "P$7") (pinfunction "D1_P$7") (pintype "bidirectional"))
      (node (ref "U15") (pin "P$8") (pinfunction "D1_P$8") (pintype "bidirectional"))
    )
    (net (code "84") (name "Net-(R55-1)") (class "Default")
      (node (ref "LIFEPO41") (pin "MINUS") (pinfunction "MINUS_MINUS") (pintype "power_in"))
      (node (ref "LIFEPO42") (pin "PLUS") (pinfunction "PLUS_PLUS") (pintype "power_in"))
      (node (ref "R47") (pin "2") (pinfunction "2_2") (pintype "passive"))
      (node (ref "R55") (pin "P$1") (pinfunction "1_P$1") (pintype "passive"))
      (node (ref "U15") (pin "P$1") (pinfunction "S1_P$1") (pintype "bidirectional"))
    )
    (net (code "85") (name "Net-(R55-2)") (class "Default")
      (node (ref "R55") (pin "P$2") (pinfunction "2_P$2") (pintype "passive"))
      (node (ref "U15") (pin "P$5") (pinfunction "D2_P$5") (pintype "bidirectional"))
      (node (ref "U15") (pin "P$6") (pinfunction "D2_P$6") (pintype "bidirectional"))
    )
    (net (code "86") (name "Net-(R72-1)") (class "Default")
      (node (ref "R72") (pin "P$1") (pinfunction "1_P$1") (pintype "passive"))
      (node (ref "U17") (pin "P$7") (pinfunction "D1_P$7") (pintype "bidirectional"))
      (node (ref "U17") (pin "P$8") (pinfunction "D1_P$8") (pintype "bidirectional"))
    )
    (net (code "87") (name "Net-(R73-1)") (class "Default")
      (node (ref "LIFEPO43") (pin "MINUS") (pinfunction "MINUS_MINUS") (pintype "power_in"))
      (node (ref "LIFEPO44") (pin "PLUS") (pinfunction "PLUS_PLUS") (pintype "power_in"))
      (node (ref "R65") (pin "2") (pinfunction "2_2") (pintype "passive"))
      (node (ref "R73") (pin "P$1") (pinfunction "1_P$1") (pintype "passive"))
      (node (ref "U17") (pin "P$1") (pinfunction "S1_P$1") (pintype "bidirectional"))
    )
    (net (code "88") (name "Net-(R73-2)") (class "Default")
      (node (ref "R73") (pin "P$2") (pinfunction "2_P$2") (pintype "passive"))
      (node (ref "U17") (pin "P$5") (pinfunction "D2_P$5") (pintype "bidirectional"))
      (node (ref "U17") (pin "P$6") (pinfunction "D2_P$6") (pintype "bidirectional"))
    )
    (net (code "89") (name "Net-(SW1-ISNS)") (class "Default")
      (node (ref "R58") (pin "2") (pinfunction "2_2") (pintype "passive"))
      (node (ref "R79") (pin "2") (pinfunction "2_2") (pintype "passive"))
      (node (ref "SW1") (pin "P$3") (pinfunction "ISNS_P$3") (pintype "output"))
    )
    (net (code "90") (name "Net-(SW2-ISNS)") (class "Default")
      (node (ref "R76") (pin "2") (pinfunction "2_2") (pintype "passive"))
      (node (ref "R82") (pin "2") (pinfunction "2_2") (pintype "passive"))
      (node (ref "SW2") (pin "P$3") (pinfunction "ISNS_P$3") (pintype "output"))
    )
    (net (code "91") (name "Net-(U1-P03)") (class "Default")
      (node (ref "R32") (pin "2") (pinfunction "2_2") (pintype "passive"))
      (node (ref "U1") (pin "P$7") (pinfunction "P03_P$7") (pintype "bidirectional"))
    )
    (net (code "92") (name "Net-(U4-CHGSNS)") (class "Default")
      (node (ref "L1") (pin "P$2") (pinfunction "P$2_P$2") (pintype "passive"))
      (node (ref "U4") (pin "P$8") (pinfunction "CHGSNS_P$8") (pintype "bidirectional"))
    )
    (net (code "93") (name "Net-(U4-MPPT)") (class "Default")
      (node (ref "R27") (pin "1") (pinfunction "1_1") (pintype "passive"))
      (node (ref "R28") (pin "2") (pinfunction "2_2") (pintype "passive"))
      (node (ref "U4") (pin "P$6") (pinfunction "MPPT_P$6") (pintype "bidirectional"))
    )
    (net (code "94") (name "Net-(U5-CHGSNS)") (class "Default")
      (node (ref "L2") (pin "P$2") (pinfunction "P$2_P$2") (pintype "passive"))
      (node (ref "U5") (pin "P$8") (pinfunction "CHGSNS_P$8") (pintype "bidirectional"))
    )
    (net (code "95") (name "Net-(U5-MPPT)") (class "Default")
      (node (ref "R10") (pin "1") (pinfunction "1_1") (pintype "passive"))
      (node (ref "R11") (pin "2") (pinfunction "2_2") (pintype "passive"))
      (node (ref "U5") (pin "P$6") (pinfunction "MPPT_P$6") (pintype "bidirectional"))
    )
    (net (code "96") (name "Net-(U6-CS)") (class "Default")
      (node (ref "R8") (pin "2") (pinfunction "2_2") (pintype "passive"))
      (node (ref "U6") (pin "P$2") (pinfunction "CS_P$2") (pintype "bidirectional"))
    )
    (net (code "97") (name "Net-(U6-S1)") (class "Default")
      (node (ref "U6") (pin "P$6") (pinfunction "S1_P$6") (pintype "bidirectional"))
      (node (ref "V23") (pin "P$1") (pinfunction "P$1_P$1") (pintype "bidirectional"))
    )
    (net (code "98") (name "Net-(U7-CS)") (class "Default")
      (node (ref "R23") (pin "2") (pinfunction "2_2") (pintype "passive"))
      (node (ref "U7") (pin "P$2") (pinfunction "CS_P$2") (pintype "bidirectional"))
    )
    (net (code "99") (name "Net-(U7-S1)") (class "Default")
      (node (ref "U7") (pin "P$6") (pinfunction "S1_P$6") (pintype "bidirectional"))
      (node (ref "V25") (pin "P$1") (pinfunction "P$1_P$1") (pintype "bidirectional"))
    )
    (net (code "100") (name "Net-(U8-VREF1)") (class "Default")
      (node (ref "R4") (pin "2") (pinfunction "2_2") (pintype "passive"))
      (node (ref "R6") (pin "1") (pinfunction "1_1") (pintype "passive"))
      (node (ref "U8") (pin "P$3") (pinfunction "VREF2_P$3") (pintype "bidirectional"))
      (node (ref "U8") (pin "P$7") (pinfunction "VREF1_P$7") (pintype "bidirectional"))
    )
    (net (code "101") (name "Net-(U9-VREF1)") (class "Default")
      (node (ref "R20") (pin "2") (pinfunction "2_2") (pintype "passive"))
      (node (ref "R21") (pin "1") (pinfunction "1_1") (pintype "passive"))
      (node (ref "U9") (pin "P$3") (pinfunction "VREF2_P$3") (pintype "bidirectional"))
      (node (ref "U9") (pin "P$7") (pinfunction "VREF1_P$7") (pintype "bidirectional"))
    )
    (net (code "102") (name "Net-(U14-CHGSNS)") (class "Default")
      (node (ref "L3") (pin "P$1") (pinfunction "P$1_P$1") (pintype "passive"))
      (node (ref "U14") (pin "P$8") (pinfunction "CHGSNS_P$8") (pintype "bidirectional"))
    )
    (net (code "103") (name "Net-(U14-FB)") (class "Default")
      (node (ref "R52") (pin "2") (pinfunction "2_2") (pintype "passive"))
      (node (ref "R53") (pin "1") (pinfunction "1_1") (pintype "passive"))
      (node (ref "U14") (pin "P$10") (pinfunction "FB_P$10") (pintype "bidirectional"))
    )
    (net (code "104") (name "Net-(U14-FBG)") (class "Default")
      (node (ref "R52") (pin "1") (pinfunction "1_1") (pintype "passive"))
      (node (ref "U14") (pin "P$11") (pinfunction "FBG_P$11") (pintype "bidirectional"))
    )
    (net (code "105") (name "Net-(U14-MPPT)") (class "Default")
      (node (ref "R45") (pin "1") (pinfunction "1_1") (pintype "passive"))
      (node (ref "R46") (pin "2") (pinfunction "2_2") (pintype "passive"))
      (node (ref "U14") (pin "P$6") (pinfunction "MPPT_P$6") (pintype "bidirectional"))
    )
    (net (code "106") (name "Net-(U14-PROG)") (class "Default")
      (node (ref "R51") (pin "1") (pinfunction "1_1") (pintype "passive"))
      (node (ref "U14") (pin "P$13") (pinfunction "PROG_P$13") (pintype "bidirectional"))
    )
    (net (code "107") (name "Net-(U16-CHGSNS)") (class "Default")
      (node (ref "L4") (pin "P$1") (pinfunction "P$1_P$1") (pintype "passive"))
      (node (ref "U16") (pin "P$8") (pinfunction "CHGSNS_P$8") (pintype "bidirectional"))
    )
    (net (code "108") (name "Net-(U16-FB)") (class "Default")
      (node (ref "R70") (pin "2") (pinfunction "2_2") (pintype "passive"))
      (node (ref "R71") (pin "1") (pinfunction "1_1") (pintype "passive"))
      (node (ref "U16") (pin "P$10") (pinfunction "FB_P$10") (pintype "bidirectional"))
    )
    (net (code "109") (name "Net-(U16-FBG)") (class "Default")
      (node (ref "R70") (pin "1") (pinfunction "1_1") (pintype "passive"))
      (node (ref "U16") (pin "P$11") (pinfunction "FBG_P$11") (pintype "bidirectional"))
    )
    (net (code "110") (name "Net-(U16-MPPT)") (class "Default")
      (node (ref "R63") (pin "1") (pinfunction "1_1") (pintype "passive"))
      (node (ref "R64") (pin "2") (pinfunction "2_2") (pintype "passive"))
      (node (ref "U16") (pin "P$6") (pinfunction "MPPT_P$6") (pintype "bidirectional"))
    )
    (net (code "111") (name "Net-(U16-PROG)") (class "Default")
      (node (ref "R69") (pin "1") (pinfunction "1_1") (pintype "passive"))
      (node (ref "U16") (pin "P$13") (pinfunction "PROG_P$13") (pintype "bidirectional"))
    )
    (net (code "112") (name "Net-(U18-VREF1)") (class "Default")
      (node (ref "R24") (pin "2") (pinfunction "2_2") (pintype "passive"))
      (node (ref "R26") (pin "1") (pinfunction "1_1") (pintype "passive"))
      (node (ref "U18") (pin "P$3") (pinfunction "VREF2_P$3") (pintype "bidirectional"))
      (node (ref "U18") (pin "P$7") (pinfunction "VREF1_P$7") (pintype "bidirectional"))
    )
    (net (code "113") (name "Net-(U19-VREF1)") (class "Default")
      (node (ref "R29") (pin "2") (pinfunction "2_2") (pintype "passive"))
      (node (ref "R30") (pin "1") (pinfunction "1_1") (pintype "passive"))
      (node (ref "U19") (pin "P$3") (pinfunction "VREF2_P$3") (pintype "bidirectional"))
      (node (ref "U19") (pin "P$7") (pinfunction "VREF1_P$7") (pintype "bidirectional"))
    )
    (net (code "114") (name "PANELREF") (class "Default")
      (node (ref "R13") (pin "1") (pinfunction "1_1") (pintype "passive"))
      (node (ref "R14") (pin "2") (pinfunction "2_2") (pintype "passive"))
      (node (ref "U2") (pin "P$6") (pinfunction "VIN3/REF_P$6") (pintype "bidirectional"))
    )
    (net (code "115") (name "SCL") (class "Default")
      (node (ref "R85") (pin "1") (pinfunction "1_1") (pintype "passive"))
      (node (ref "U1") (pin "P$22") (pinfunction "SCL_P$22") (pintype "bidirectional"))
      (node (ref "U2") (pin "P$1") (pinfunction "SCL_P$1") (pintype "bidirectional"))
      (node (ref "V5") (pin "P$1") (pinfunction "P$1_P$1") (pintype "bidirectional"))
    )
    (net (code "116") (name "SDA") (class "Default")
      (node (ref "R86") (pin "1") (pinfunction "1_1") (pintype "passive"))
      (node (ref "U1") (pin "P$23") (pinfunction "SDA_P$23") (pintype "bidirectional"))
      (node (ref "U2") (pin "P$2") (pinfunction "SDA_P$2") (pintype "bidirectional"))
      (node (ref "V6") (pin "P$1") (pinfunction "P$1_P$1") (pintype "bidirectional"))
    )
    (net (code "117") (name "SPF_ST") (class "Default")
      (node (ref "R83") (pin "1") (pinfunction "1_1") (pintype "passive"))
      (node (ref "U1") (pin "P$6") (pinfunction "P02_P$6") (pintype "bidirectional"))
      (node (ref "U3") (pin "P$4") (pinfunction "STAT_P$4") (pintype "bidirectional"))
    )
    (net (code "118") (name "SP_C") (class "Default")
      (node (ref "C3") (pin "1") (pinfunction "P$1_1") (pintype "passive"))
      (node (ref "M1") (pin "P$5") (pinfunction "D_P$5") (pintype "bidirectional"))
      (node (ref "M1") (pin "P$6") (pinfunction "D_P$6") (pintype "bidirectional"))
      (node (ref "M1") (pin "P$7") (pinfunction "D_P$7") (pintype "bidirectional"))
      (node (ref "M1") (pin "P$8") (pinfunction "D_P$8") (pintype "bidirectional"))
      (node (ref "R5") (pin "1") (pinfunction "1_1") (pintype "passive"))
      (node (ref "U3") (pin "P$1") (pinfunction "VIN_P$1") (pintype "bidirectional"))
      (node (ref "V13") (pin "P$1") (pinfunction "P$1_P$1") (pintype "bidirectional"))
      (node (ref "V14") (pin "P$1") (pinfunction "P$1_P$1") (pintype "bidirectional"))
      (node (ref "V15") (pin "P$1") (pinfunction "P$1_P$1") (pintype "bidirectional"))
      (node (ref "V16") (pin "P$1") (pinfunction "P$1_P$1") (pintype "bidirectional"))
      (node (ref "V17") (pin "P$1") (pinfunction "P$1_P$1") (pintype "bidirectional"))
      (node (ref "V18") (pin "P$1") (pinfunction "P$1_P$1") (pintype "bidirectional"))
    )
    (net (code "119") (name "SP_OUT") (class "Default")
      (node (ref "C17") (pin "1") (pinfunction "P$1_1") (pintype "passive"))
      (node (ref "C18") (pin "1") (pinfunction "P$1_1") (pintype "passive"))
      (node (ref "C25") (pin "2") (pinfunction "P$2_2") (pintype "passive"))
      (node (ref "C32") (pin "2") (pinfunction "P$2_2") (pintype "passive"))
      (node (ref "C4") (pin "1") (pinfunction "P$1_1") (pintype "passive"))
      (node (ref "C5") (pin "1") (pinfunction "P$1_1") (pintype "passive"))
      (node (ref "C6") (pin "1") (pinfunction "P$1_1") (pintype "passive"))
      (node (ref "D1") (pin "C") (pinfunction "C_C") (pintype "bidirectional"))
      (node (ref "M1") (pin "P$1") (pinfunction "S_P$1") (pintype "bidirectional"))
      (node (ref "M1") (pin "P$2") (pinfunction "S_P$2") (pintype "bidirectional"))
      (node (ref "M1") (pin "P$3") (pinfunction "S_P$3") (pintype "bidirectional"))
      (node (ref "R1") (pin "1") (pinfunction "1_1") (pintype "passive"))
      (node (ref "R10") (pin "2") (pinfunction "2_2") (pintype "passive"))
      (node (ref "R13") (pin "2") (pinfunction "2_2") (pintype "passive"))
      (node (ref "R15") (pin "1") (pinfunction "1_1") (pintype "passive"))
      (node (ref "R27") (pin "2") (pinfunction "2_2") (pintype "passive"))
      (node (ref "R45") (pin "2") (pinfunction "2_2") (pintype "passive"))
      (node (ref "R5") (pin "2") (pinfunction "2_2") (pintype "passive"))
      (node (ref "R63") (pin "2") (pinfunction "2_2") (pintype "passive"))
      (node (ref "U10") (pin "P$5") (pinfunction "~{SHDN}_P$5") (pintype "bidirectional"))
      (node (ref "U10") (pin "P$8") (pinfunction "IN_P$8") (pintype "bidirectional"))
      (node (ref "U11") (pin "P$5") (pinfunction "~{SHDN}_P$5") (pintype "bidirectional"))
      (node (ref "U11") (pin "P$8") (pinfunction "IN_P$8") (pintype "bidirectional"))
      (node (ref "U14") (pin "P$3") (pinfunction "IN_P$3") (pintype "bidirectional"))
      (node (ref "U16") (pin "P$3") (pinfunction "IN_P$3") (pintype "bidirectional"))
      (node (ref "U3") (pin "P$6") (pinfunction "SNS_P$6") (pintype "bidirectional"))
      (node (ref "U4") (pin "P$3") (pinfunction "IN_P$3") (pintype "bidirectional"))
      (node (ref "U5") (pin "P$3") (pinfunction "IN_P$3") (pintype "bidirectional"))
    )
    (net (code "120") (name "UMB_CHG") (class "Default")
      (node (ref "D1") (pin "A") (pinfunction "A_A") (pintype "bidirectional"))
      (node (ref "V19") (pin "P$1") (pinfunction "P$1_P$1") (pintype "bidirectional"))
    )
    (net (code "121") (name "~{BATT_INT}") (class "Default")
      (node (ref "R84") (pin "1") (pinfunction "1_1") (pintype "passive"))
      (node (ref "U1") (pin "P$1") (pinfunction "~{INT}_P$1") (pintype "bidirectional"))
    )
  )
)
